# LEDSubMatrixHighDensity_template.net
KiCad netlist of a schematic drawn in EAGLE
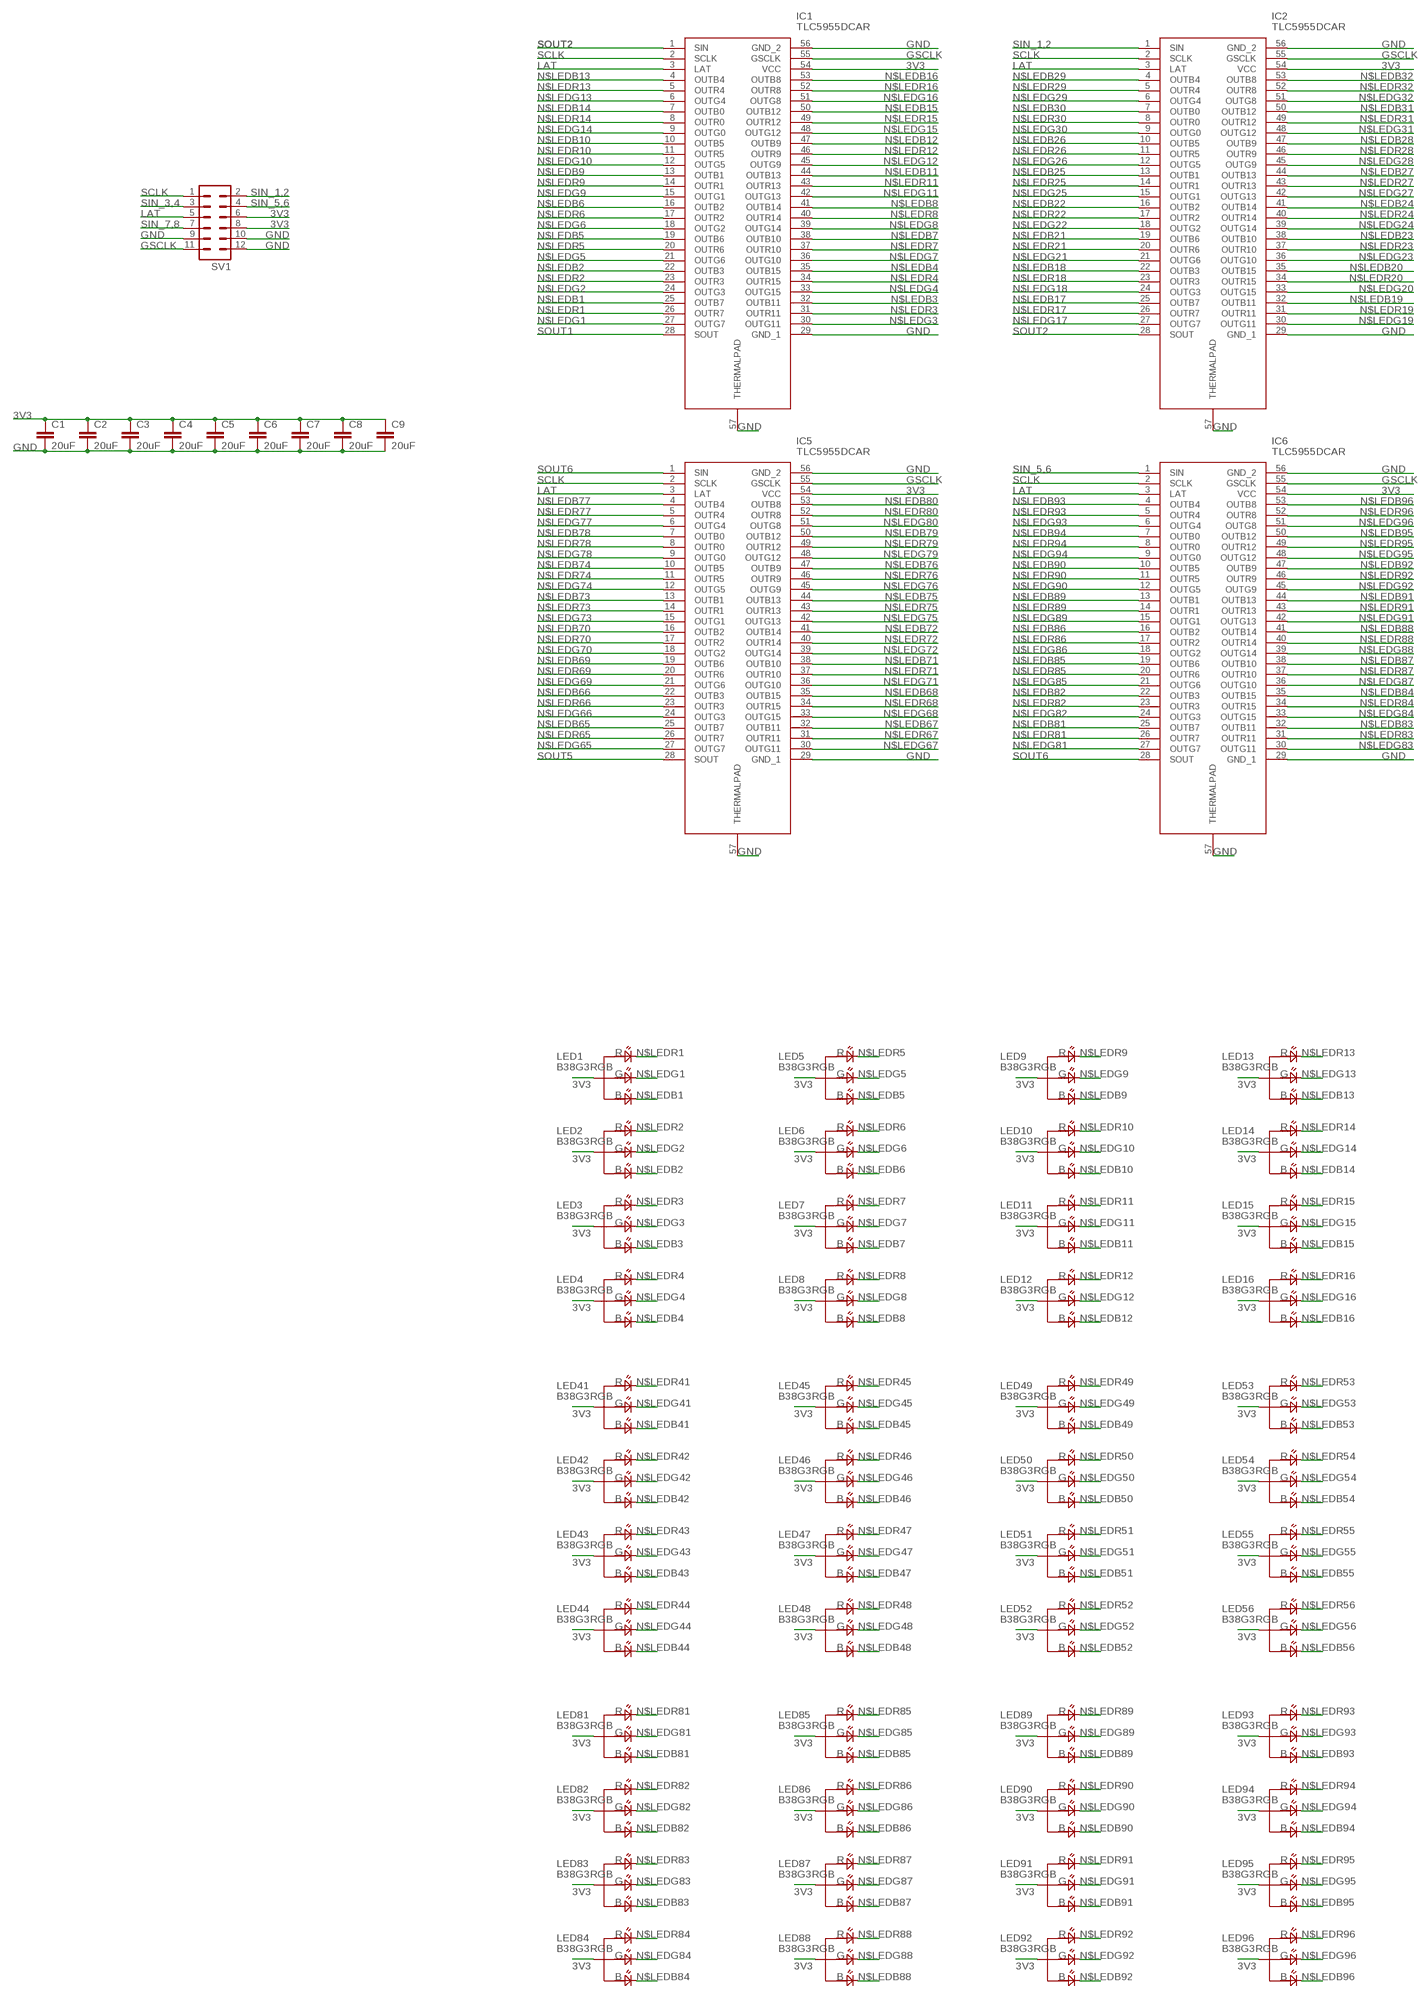
[diagram p0: schematic, sheet 1, part 1 of 2]
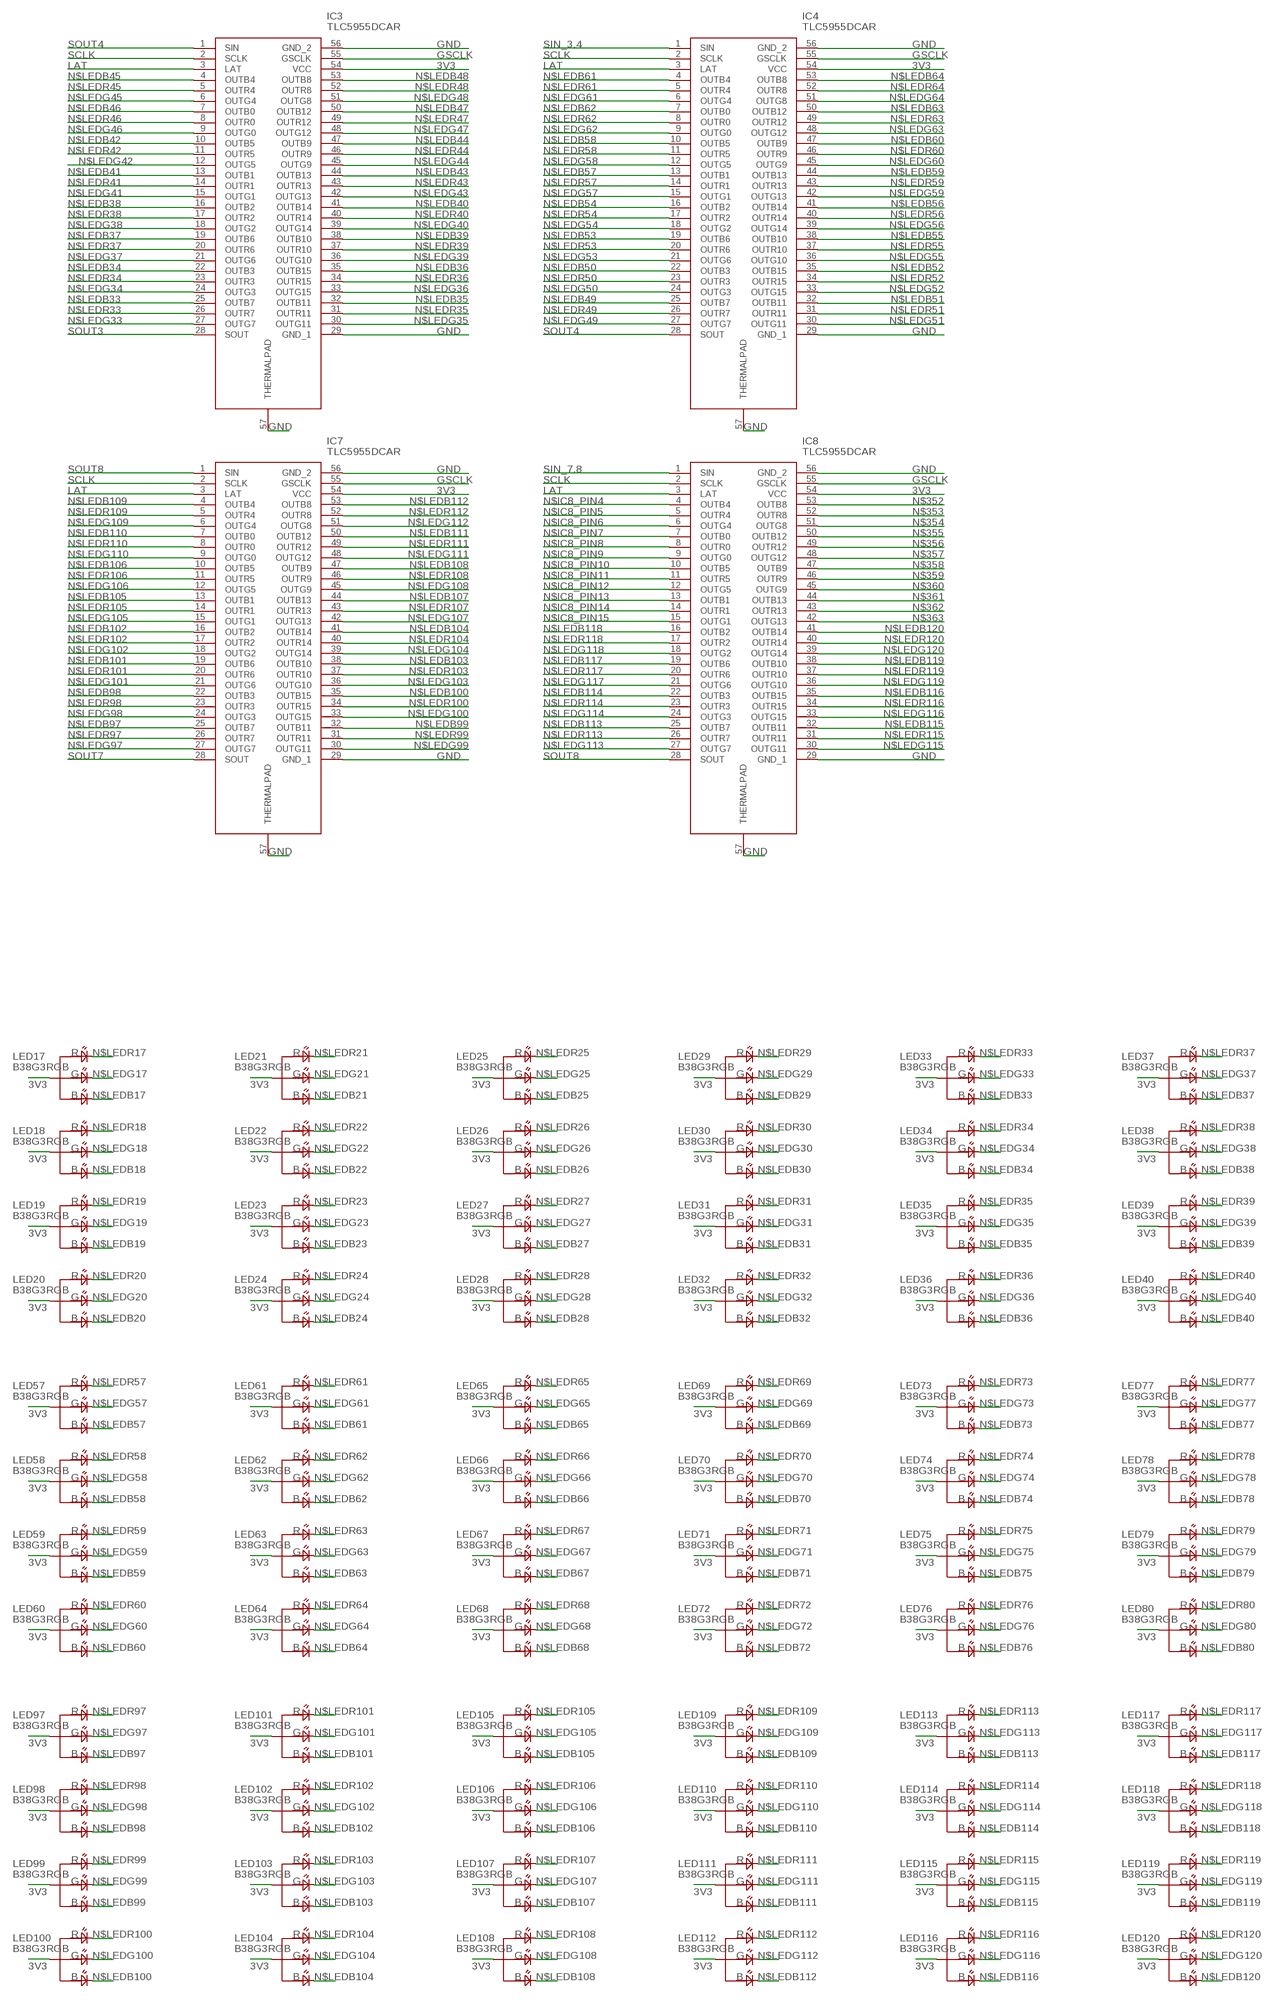
[diagram p1: schematic, sheet 1, part 2 of 2]

(export (version "E")
  (design (tool "Eeschema 10.0.6"))
  (components
    (comp (ref "C1")
      (value "20uF")
      (footprint "eagle-import:C0603")
      (libsource (lib "eagle-import") (part "C-EUC0603"))
    )
    (comp (ref "C2")
      (value "20uF")
      (footprint "eagle-import:C0603")
      (libsource (lib "eagle-import") (part "C-EUC0603"))
    )
    (comp (ref "C3")
      (value "20uF")
      (footprint "eagle-import:C0603")
      (libsource (lib "eagle-import") (part "C-EUC0603"))
    )
    (comp (ref "C4")
      (value "20uF")
      (footprint "eagle-import:C0603")
      (libsource (lib "eagle-import") (part "C-EUC0603"))
    )
    (comp (ref "C5")
      (value "20uF")
      (footprint "eagle-import:C0603")
      (libsource (lib "eagle-import") (part "C-EUC0603"))
    )
    (comp (ref "C6")
      (value "20uF")
      (footprint "eagle-import:C0603")
      (libsource (lib "eagle-import") (part "C-EUC0603"))
    )
    (comp (ref "C7")
      (value "20uF")
      (footprint "eagle-import:C0603")
      (libsource (lib "eagle-import") (part "C-EUC0603"))
    )
    (comp (ref "C8")
      (value "20uF")
      (footprint "eagle-import:C0603")
      (libsource (lib "eagle-import") (part "C-EUC0603"))
    )
    (comp (ref "C9")
      (value "20uF")
      (footprint "eagle-import:C0805")
      (libsource (lib "eagle-import") (part "C-EUC0805"))
    )
    (comp (ref "IC1")
      (value "TLC5955DCAR")
      (footprint "eagle-import:SOP50P810X120-57N")
      (fields (field (name "MOUSER_PART_NUMBER") "595-TLC5955DCAR"))
      (libsource (lib "eagle-import") (part "TLC5955DCAR"))
    )
    (comp (ref "IC2")
      (value "TLC5955DCAR")
      (footprint "eagle-import:SOP50P810X120-57N")
      (fields (field (name "MOUSER_PART_NUMBER") "595-TLC5955DCAR"))
      (libsource (lib "eagle-import") (part "TLC5955DCAR"))
    )
    (comp (ref "IC3")
      (value "TLC5955DCAR")
      (footprint "eagle-import:SOP50P810X120-57N")
      (fields (field (name "MOUSER_PART_NUMBER") "595-TLC5955DCAR"))
      (libsource (lib "eagle-import") (part "TLC5955DCAR"))
    )
    (comp (ref "IC4")
      (value "TLC5955DCAR")
      (footprint "eagle-import:SOP50P810X120-57N")
      (fields (field (name "MOUSER_PART_NUMBER") "595-TLC5955DCAR"))
      (libsource (lib "eagle-import") (part "TLC5955DCAR"))
    )
    (comp (ref "IC5")
      (value "TLC5955DCAR")
      (footprint "eagle-import:SOP50P810X120-57N")
      (fields (field (name "MOUSER_PART_NUMBER") "595-TLC5955DCAR"))
      (libsource (lib "eagle-import") (part "TLC5955DCAR"))
    )
    (comp (ref "IC6")
      (value "TLC5955DCAR")
      (footprint "eagle-import:SOP50P810X120-57N")
      (fields (field (name "MOUSER_PART_NUMBER") "595-TLC5955DCAR"))
      (libsource (lib "eagle-import") (part "TLC5955DCAR"))
    )
    (comp (ref "IC7")
      (value "TLC5955DCAR")
      (footprint "eagle-import:SOP50P810X120-57N")
      (fields (field (name "MOUSER_PART_NUMBER") "595-TLC5955DCAR"))
      (libsource (lib "eagle-import") (part "TLC5955DCAR"))
    )
    (comp (ref "IC8")
      (value "TLC5955DCAR")
      (footprint "eagle-import:SOP50P810X120-57N")
      (fields (field (name "MOUSER_PART_NUMBER") "595-TLC5955DCAR"))
      (libsource (lib "eagle-import") (part "TLC5955DCAR"))
    )
    (comp (ref "LED1")
      (value "B38G3RGB")
      (footprint "eagle-import:B38G3RGB")
      (fields
        (field (name "ARROW_PART_NUMBER") "SML-LX0606IGC-TR")
        (field (name "MOUSER_PART_NUMBER") "696-SML-0606IGCTR")
      )
      (libsource (lib "eagle-import") (part "B38G3RGB"))
    )
    (comp (ref "LED2")
      (value "B38G3RGB")
      (footprint "eagle-import:B38G3RGB")
      (fields
        (field (name "ARROW_PART_NUMBER") "SML-LX0606IGC-TR")
        (field (name "MOUSER_PART_NUMBER") "696-SML-0606IGCTR")
      )
      (libsource (lib "eagle-import") (part "B38G3RGB"))
    )
    (comp (ref "LED3")
      (value "B38G3RGB")
      (footprint "eagle-import:B38G3RGB")
      (fields
        (field (name "ARROW_PART_NUMBER") "SML-LX0606IGC-TR")
        (field (name "MOUSER_PART_NUMBER") "696-SML-0606IGCTR")
      )
      (libsource (lib "eagle-import") (part "B38G3RGB"))
    )
    (comp (ref "LED4")
      (value "B38G3RGB")
      (footprint "eagle-import:B38G3RGB")
      (fields
        (field (name "ARROW_PART_NUMBER") "SML-LX0606IGC-TR")
        (field (name "MOUSER_PART_NUMBER") "696-SML-0606IGCTR")
      )
      (libsource (lib "eagle-import") (part "B38G3RGB"))
    )
    (comp (ref "LED5")
      (value "B38G3RGB")
      (footprint "eagle-import:B38G3RGB")
      (fields
        (field (name "ARROW_PART_NUMBER") "SML-LX0606IGC-TR")
        (field (name "MOUSER_PART_NUMBER") "696-SML-0606IGCTR")
      )
      (libsource (lib "eagle-import") (part "B38G3RGB"))
    )
    (comp (ref "LED6")
      (value "B38G3RGB")
      (footprint "eagle-import:B38G3RGB")
      (fields
        (field (name "ARROW_PART_NUMBER") "SML-LX0606IGC-TR")
        (field (name "MOUSER_PART_NUMBER") "696-SML-0606IGCTR")
      )
      (libsource (lib "eagle-import") (part "B38G3RGB"))
    )
    (comp (ref "LED7")
      (value "B38G3RGB")
      (footprint "eagle-import:B38G3RGB")
      (fields
        (field (name "ARROW_PART_NUMBER") "SML-LX0606IGC-TR")
        (field (name "MOUSER_PART_NUMBER") "696-SML-0606IGCTR")
      )
      (libsource (lib "eagle-import") (part "B38G3RGB"))
    )
    (comp (ref "LED8")
      (value "B38G3RGB")
      (footprint "eagle-import:B38G3RGB")
      (fields
        (field (name "ARROW_PART_NUMBER") "SML-LX0606IGC-TR")
        (field (name "MOUSER_PART_NUMBER") "696-SML-0606IGCTR")
      )
      (libsource (lib "eagle-import") (part "B38G3RGB"))
    )
    (comp (ref "LED9")
      (value "B38G3RGB")
      (footprint "eagle-import:B38G3RGB")
      (fields
        (field (name "ARROW_PART_NUMBER") "SML-LX0606IGC-TR")
        (field (name "MOUSER_PART_NUMBER") "696-SML-0606IGCTR")
      )
      (libsource (lib "eagle-import") (part "B38G3RGB"))
    )
    (comp (ref "LED10")
      (value "B38G3RGB")
      (footprint "eagle-import:B38G3RGB")
      (fields
        (field (name "ARROW_PART_NUMBER") "SML-LX0606IGC-TR")
        (field (name "MOUSER_PART_NUMBER") "696-SML-0606IGCTR")
      )
      (libsource (lib "eagle-import") (part "B38G3RGB"))
    )
    (comp (ref "LED11")
      (value "B38G3RGB")
      (footprint "eagle-import:B38G3RGB")
      (fields
        (field (name "ARROW_PART_NUMBER") "SML-LX0606IGC-TR")
        (field (name "MOUSER_PART_NUMBER") "696-SML-0606IGCTR")
      )
      (libsource (lib "eagle-import") (part "B38G3RGB"))
    )
    (comp (ref "LED12")
      (value "B38G3RGB")
      (footprint "eagle-import:B38G3RGB")
      (fields
        (field (name "ARROW_PART_NUMBER") "SML-LX0606IGC-TR")
        (field (name "MOUSER_PART_NUMBER") "696-SML-0606IGCTR")
      )
      (libsource (lib "eagle-import") (part "B38G3RGB"))
    )
    (comp (ref "LED13")
      (value "B38G3RGB")
      (footprint "eagle-import:B38G3RGB")
      (fields
        (field (name "ARROW_PART_NUMBER") "SML-LX0606IGC-TR")
        (field (name "MOUSER_PART_NUMBER") "696-SML-0606IGCTR")
      )
      (libsource (lib "eagle-import") (part "B38G3RGB"))
    )
    (comp (ref "LED14")
      (value "B38G3RGB")
      (footprint "eagle-import:B38G3RGB")
      (fields
        (field (name "ARROW_PART_NUMBER") "SML-LX0606IGC-TR")
        (field (name "MOUSER_PART_NUMBER") "696-SML-0606IGCTR")
      )
      (libsource (lib "eagle-import") (part "B38G3RGB"))
    )
    (comp (ref "LED15")
      (value "B38G3RGB")
      (footprint "eagle-import:B38G3RGB")
      (fields
        (field (name "ARROW_PART_NUMBER") "SML-LX0606IGC-TR")
        (field (name "MOUSER_PART_NUMBER") "696-SML-0606IGCTR")
      )
      (libsource (lib "eagle-import") (part "B38G3RGB"))
    )
    (comp (ref "LED16")
      (value "B38G3RGB")
      (footprint "eagle-import:B38G3RGB")
      (fields
        (field (name "ARROW_PART_NUMBER") "SML-LX0606IGC-TR")
        (field (name "MOUSER_PART_NUMBER") "696-SML-0606IGCTR")
      )
      (libsource (lib "eagle-import") (part "B38G3RGB"))
    )
    (comp (ref "LED17")
      (value "B38G3RGB")
      (footprint "eagle-import:B38G3RGB")
      (fields
        (field (name "ARROW_PART_NUMBER") "SML-LX0606IGC-TR")
        (field (name "MOUSER_PART_NUMBER") "696-SML-0606IGCTR")
      )
      (libsource (lib "eagle-import") (part "B38G3RGB"))
    )
    (comp (ref "LED18")
      (value "B38G3RGB")
      (footprint "eagle-import:B38G3RGB")
      (fields
        (field (name "ARROW_PART_NUMBER") "SML-LX0606IGC-TR")
        (field (name "MOUSER_PART_NUMBER") "696-SML-0606IGCTR")
      )
      (libsource (lib "eagle-import") (part "B38G3RGB"))
    )
    (comp (ref "LED19")
      (value "B38G3RGB")
      (footprint "eagle-import:B38G3RGB")
      (fields
        (field (name "ARROW_PART_NUMBER") "SML-LX0606IGC-TR")
        (field (name "MOUSER_PART_NUMBER") "696-SML-0606IGCTR")
      )
      (libsource (lib "eagle-import") (part "B38G3RGB"))
    )
    (comp (ref "LED20")
      (value "B38G3RGB")
      (footprint "eagle-import:B38G3RGB")
      (fields
        (field (name "ARROW_PART_NUMBER") "SML-LX0606IGC-TR")
        (field (name "MOUSER_PART_NUMBER") "696-SML-0606IGCTR")
      )
      (libsource (lib "eagle-import") (part "B38G3RGB"))
    )
    (comp (ref "LED21")
      (value "B38G3RGB")
      (footprint "eagle-import:B38G3RGB")
      (fields
        (field (name "ARROW_PART_NUMBER") "SML-LX0606IGC-TR")
        (field (name "MOUSER_PART_NUMBER") "696-SML-0606IGCTR")
      )
      (libsource (lib "eagle-import") (part "B38G3RGB"))
    )
    (comp (ref "LED22")
      (value "B38G3RGB")
      (footprint "eagle-import:B38G3RGB")
      (fields
        (field (name "ARROW_PART_NUMBER") "SML-LX0606IGC-TR")
        (field (name "MOUSER_PART_NUMBER") "696-SML-0606IGCTR")
      )
      (libsource (lib "eagle-import") (part "B38G3RGB"))
    )
    (comp (ref "LED23")
      (value "B38G3RGB")
      (footprint "eagle-import:B38G3RGB")
      (fields
        (field (name "ARROW_PART_NUMBER") "SML-LX0606IGC-TR")
        (field (name "MOUSER_PART_NUMBER") "696-SML-0606IGCTR")
      )
      (libsource (lib "eagle-import") (part "B38G3RGB"))
    )
    (comp (ref "LED24")
      (value "B38G3RGB")
      (footprint "eagle-import:B38G3RGB")
      (fields
        (field (name "ARROW_PART_NUMBER") "SML-LX0606IGC-TR")
        (field (name "MOUSER_PART_NUMBER") "696-SML-0606IGCTR")
      )
      (libsource (lib "eagle-import") (part "B38G3RGB"))
    )
    (comp (ref "LED25")
      (value "B38G3RGB")
      (footprint "eagle-import:B38G3RGB")
      (fields
        (field (name "ARROW_PART_NUMBER") "SML-LX0606IGC-TR")
        (field (name "MOUSER_PART_NUMBER") "696-SML-0606IGCTR")
      )
      (libsource (lib "eagle-import") (part "B38G3RGB"))
    )
    (comp (ref "LED26")
      (value "B38G3RGB")
      (footprint "eagle-import:B38G3RGB")
      (fields
        (field (name "ARROW_PART_NUMBER") "SML-LX0606IGC-TR")
        (field (name "MOUSER_PART_NUMBER") "696-SML-0606IGCTR")
      )
      (libsource (lib "eagle-import") (part "B38G3RGB"))
    )
    (comp (ref "LED27")
      (value "B38G3RGB")
      (footprint "eagle-import:B38G3RGB")
      (fields
        (field (name "ARROW_PART_NUMBER") "SML-LX0606IGC-TR")
        (field (name "MOUSER_PART_NUMBER") "696-SML-0606IGCTR")
      )
      (libsource (lib "eagle-import") (part "B38G3RGB"))
    )
    (comp (ref "LED28")
      (value "B38G3RGB")
      (footprint "eagle-import:B38G3RGB")
      (fields
        (field (name "ARROW_PART_NUMBER") "SML-LX0606IGC-TR")
        (field (name "MOUSER_PART_NUMBER") "696-SML-0606IGCTR")
      )
      (libsource (lib "eagle-import") (part "B38G3RGB"))
    )
    (comp (ref "LED29")
      (value "B38G3RGB")
      (footprint "eagle-import:B38G3RGB")
      (fields
        (field (name "ARROW_PART_NUMBER") "SML-LX0606IGC-TR")
        (field (name "MOUSER_PART_NUMBER") "696-SML-0606IGCTR")
      )
      (libsource (lib "eagle-import") (part "B38G3RGB"))
    )
    (comp (ref "LED30")
      (value "B38G3RGB")
      (footprint "eagle-import:B38G3RGB")
      (fields
        (field (name "ARROW_PART_NUMBER") "SML-LX0606IGC-TR")
        (field (name "MOUSER_PART_NUMBER") "696-SML-0606IGCTR")
      )
      (libsource (lib "eagle-import") (part "B38G3RGB"))
    )
    (comp (ref "LED31")
      (value "B38G3RGB")
      (footprint "eagle-import:B38G3RGB")
      (fields
        (field (name "ARROW_PART_NUMBER") "SML-LX0606IGC-TR")
        (field (name "MOUSER_PART_NUMBER") "696-SML-0606IGCTR")
      )
      (libsource (lib "eagle-import") (part "B38G3RGB"))
    )
    (comp (ref "LED32")
      (value "B38G3RGB")
      (footprint "eagle-import:B38G3RGB")
      (fields
        (field (name "ARROW_PART_NUMBER") "SML-LX0606IGC-TR")
        (field (name "MOUSER_PART_NUMBER") "696-SML-0606IGCTR")
      )
      (libsource (lib "eagle-import") (part "B38G3RGB"))
    )
    (comp (ref "LED33")
      (value "B38G3RGB")
      (footprint "eagle-import:B38G3RGB")
      (fields
        (field (name "ARROW_PART_NUMBER") "SML-LX0606IGC-TR")
        (field (name "MOUSER_PART_NUMBER") "696-SML-0606IGCTR")
      )
      (libsource (lib "eagle-import") (part "B38G3RGB"))
    )
    (comp (ref "LED34")
      (value "B38G3RGB")
      (footprint "eagle-import:B38G3RGB")
      (fields
        (field (name "ARROW_PART_NUMBER") "SML-LX0606IGC-TR")
        (field (name "MOUSER_PART_NUMBER") "696-SML-0606IGCTR")
      )
      (libsource (lib "eagle-import") (part "B38G3RGB"))
    )
    (comp (ref "LED35")
      (value "B38G3RGB")
      (footprint "eagle-import:B38G3RGB")
      (fields
        (field (name "ARROW_PART_NUMBER") "SML-LX0606IGC-TR")
        (field (name "MOUSER_PART_NUMBER") "696-SML-0606IGCTR")
      )
      (libsource (lib "eagle-import") (part "B38G3RGB"))
    )
    (comp (ref "LED36")
      (value "B38G3RGB")
      (footprint "eagle-import:B38G3RGB")
      (fields
        (field (name "ARROW_PART_NUMBER") "SML-LX0606IGC-TR")
        (field (name "MOUSER_PART_NUMBER") "696-SML-0606IGCTR")
      )
      (libsource (lib "eagle-import") (part "B38G3RGB"))
    )
    (comp (ref "LED37")
      (value "B38G3RGB")
      (footprint "eagle-import:B38G3RGB")
      (fields
        (field (name "ARROW_PART_NUMBER") "SML-LX0606IGC-TR")
        (field (name "MOUSER_PART_NUMBER") "696-SML-0606IGCTR")
      )
      (libsource (lib "eagle-import") (part "B38G3RGB"))
    )
    (comp (ref "LED38")
      (value "B38G3RGB")
      (footprint "eagle-import:B38G3RGB")
      (fields
        (field (name "ARROW_PART_NUMBER") "SML-LX0606IGC-TR")
        (field (name "MOUSER_PART_NUMBER") "696-SML-0606IGCTR")
      )
      (libsource (lib "eagle-import") (part "B38G3RGB"))
    )
    (comp (ref "LED39")
      (value "B38G3RGB")
      (footprint "eagle-import:B38G3RGB")
      (fields
        (field (name "ARROW_PART_NUMBER") "SML-LX0606IGC-TR")
        (field (name "MOUSER_PART_NUMBER") "696-SML-0606IGCTR")
      )
      (libsource (lib "eagle-import") (part "B38G3RGB"))
    )
    (comp (ref "LED40")
      (value "B38G3RGB")
      (footprint "eagle-import:B38G3RGB")
      (fields
        (field (name "ARROW_PART_NUMBER") "SML-LX0606IGC-TR")
        (field (name "MOUSER_PART_NUMBER") "696-SML-0606IGCTR")
      )
      (libsource (lib "eagle-import") (part "B38G3RGB"))
    )
    (comp (ref "LED41")
      (value "B38G3RGB")
      (footprint "eagle-import:B38G3RGB")
      (fields
        (field (name "ARROW_PART_NUMBER") "SML-LX0606IGC-TR")
        (field (name "MOUSER_PART_NUMBER") "696-SML-0606IGCTR")
      )
      (libsource (lib "eagle-import") (part "B38G3RGB"))
    )
    (comp (ref "LED42")
      (value "B38G3RGB")
      (footprint "eagle-import:B38G3RGB")
      (fields
        (field (name "ARROW_PART_NUMBER") "SML-LX0606IGC-TR")
        (field (name "MOUSER_PART_NUMBER") "696-SML-0606IGCTR")
      )
      (libsource (lib "eagle-import") (part "B38G3RGB"))
    )
    (comp (ref "LED43")
      (value "B38G3RGB")
      (footprint "eagle-import:B38G3RGB")
      (fields
        (field (name "ARROW_PART_NUMBER") "SML-LX0606IGC-TR")
        (field (name "MOUSER_PART_NUMBER") "696-SML-0606IGCTR")
      )
      (libsource (lib "eagle-import") (part "B38G3RGB"))
    )
    (comp (ref "LED44")
      (value "B38G3RGB")
      (footprint "eagle-import:B38G3RGB")
      (fields
        (field (name "ARROW_PART_NUMBER") "SML-LX0606IGC-TR")
        (field (name "MOUSER_PART_NUMBER") "696-SML-0606IGCTR")
      )
      (libsource (lib "eagle-import") (part "B38G3RGB"))
    )
    (comp (ref "LED45")
      (value "B38G3RGB")
      (footprint "eagle-import:B38G3RGB")
      (fields
        (field (name "ARROW_PART_NUMBER") "SML-LX0606IGC-TR")
        (field (name "MOUSER_PART_NUMBER") "696-SML-0606IGCTR")
      )
      (libsource (lib "eagle-import") (part "B38G3RGB"))
    )
    (comp (ref "LED46")
      (value "B38G3RGB")
      (footprint "eagle-import:B38G3RGB")
      (fields
        (field (name "ARROW_PART_NUMBER") "SML-LX0606IGC-TR")
        (field (name "MOUSER_PART_NUMBER") "696-SML-0606IGCTR")
      )
      (libsource (lib "eagle-import") (part "B38G3RGB"))
    )
    (comp (ref "LED47")
      (value "B38G3RGB")
      (footprint "eagle-import:B38G3RGB")
      (fields
        (field (name "ARROW_PART_NUMBER") "SML-LX0606IGC-TR")
        (field (name "MOUSER_PART_NUMBER") "696-SML-0606IGCTR")
      )
      (libsource (lib "eagle-import") (part "B38G3RGB"))
    )
    (comp (ref "LED48")
      (value "B38G3RGB")
      (footprint "eagle-import:B38G3RGB")
      (fields
        (field (name "ARROW_PART_NUMBER") "SML-LX0606IGC-TR")
        (field (name "MOUSER_PART_NUMBER") "696-SML-0606IGCTR")
      )
      (libsource (lib "eagle-import") (part "B38G3RGB"))
    )
    (comp (ref "LED49")
      (value "B38G3RGB")
      (footprint "eagle-import:B38G3RGB")
      (fields
        (field (name "ARROW_PART_NUMBER") "SML-LX0606IGC-TR")
        (field (name "MOUSER_PART_NUMBER") "696-SML-0606IGCTR")
      )
      (libsource (lib "eagle-import") (part "B38G3RGB"))
    )
    (comp (ref "LED50")
      (value "B38G3RGB")
      (footprint "eagle-import:B38G3RGB")
      (fields
        (field (name "ARROW_PART_NUMBER") "SML-LX0606IGC-TR")
        (field (name "MOUSER_PART_NUMBER") "696-SML-0606IGCTR")
      )
      (libsource (lib "eagle-import") (part "B38G3RGB"))
    )
    (comp (ref "LED51")
      (value "B38G3RGB")
      (footprint "eagle-import:B38G3RGB")
      (fields
        (field (name "ARROW_PART_NUMBER") "SML-LX0606IGC-TR")
        (field (name "MOUSER_PART_NUMBER") "696-SML-0606IGCTR")
      )
      (libsource (lib "eagle-import") (part "B38G3RGB"))
    )
    (comp (ref "LED52")
      (value "B38G3RGB")
      (footprint "eagle-import:B38G3RGB")
      (fields
        (field (name "ARROW_PART_NUMBER") "SML-LX0606IGC-TR")
        (field (name "MOUSER_PART_NUMBER") "696-SML-0606IGCTR")
      )
      (libsource (lib "eagle-import") (part "B38G3RGB"))
    )
    (comp (ref "LED53")
      (value "B38G3RGB")
      (footprint "eagle-import:B38G3RGB")
      (fields
        (field (name "ARROW_PART_NUMBER") "SML-LX0606IGC-TR")
        (field (name "MOUSER_PART_NUMBER") "696-SML-0606IGCTR")
      )
      (libsource (lib "eagle-import") (part "B38G3RGB"))
    )
    (comp (ref "LED54")
      (value "B38G3RGB")
      (footprint "eagle-import:B38G3RGB")
      (fields
        (field (name "ARROW_PART_NUMBER") "SML-LX0606IGC-TR")
        (field (name "MOUSER_PART_NUMBER") "696-SML-0606IGCTR")
      )
      (libsource (lib "eagle-import") (part "B38G3RGB"))
    )
    (comp (ref "LED55")
      (value "B38G3RGB")
      (footprint "eagle-import:B38G3RGB")
      (fields
        (field (name "ARROW_PART_NUMBER") "SML-LX0606IGC-TR")
        (field (name "MOUSER_PART_NUMBER") "696-SML-0606IGCTR")
      )
      (libsource (lib "eagle-import") (part "B38G3RGB"))
    )
    (comp (ref "LED56")
      (value "B38G3RGB")
      (footprint "eagle-import:B38G3RGB")
      (fields
        (field (name "ARROW_PART_NUMBER") "SML-LX0606IGC-TR")
        (field (name "MOUSER_PART_NUMBER") "696-SML-0606IGCTR")
      )
      (libsource (lib "eagle-import") (part "B38G3RGB"))
    )
    (comp (ref "LED57")
      (value "B38G3RGB")
      (footprint "eagle-import:B38G3RGB")
      (fields
        (field (name "ARROW_PART_NUMBER") "SML-LX0606IGC-TR")
        (field (name "MOUSER_PART_NUMBER") "696-SML-0606IGCTR")
      )
      (libsource (lib "eagle-import") (part "B38G3RGB"))
    )
    (comp (ref "LED58")
      (value "B38G3RGB")
      (footprint "eagle-import:B38G3RGB")
      (fields
        (field (name "ARROW_PART_NUMBER") "SML-LX0606IGC-TR")
        (field (name "MOUSER_PART_NUMBER") "696-SML-0606IGCTR")
      )
      (libsource (lib "eagle-import") (part "B38G3RGB"))
    )
    (comp (ref "LED59")
      (value "B38G3RGB")
      (footprint "eagle-import:B38G3RGB")
      (fields
        (field (name "ARROW_PART_NUMBER") "SML-LX0606IGC-TR")
        (field (name "MOUSER_PART_NUMBER") "696-SML-0606IGCTR")
      )
      (libsource (lib "eagle-import") (part "B38G3RGB"))
    )
    (comp (ref "LED60")
      (value "B38G3RGB")
      (footprint "eagle-import:B38G3RGB")
      (fields
        (field (name "ARROW_PART_NUMBER") "SML-LX0606IGC-TR")
        (field (name "MOUSER_PART_NUMBER") "696-SML-0606IGCTR")
      )
      (libsource (lib "eagle-import") (part "B38G3RGB"))
    )
    (comp (ref "LED61")
      (value "B38G3RGB")
      (footprint "eagle-import:B38G3RGB")
      (fields
        (field (name "ARROW_PART_NUMBER") "SML-LX0606IGC-TR")
        (field (name "MOUSER_PART_NUMBER") "696-SML-0606IGCTR")
      )
      (libsource (lib "eagle-import") (part "B38G3RGB"))
    )
    (comp (ref "LED62")
      (value "B38G3RGB")
      (footprint "eagle-import:B38G3RGB")
      (fields
        (field (name "ARROW_PART_NUMBER") "SML-LX0606IGC-TR")
        (field (name "MOUSER_PART_NUMBER") "696-SML-0606IGCTR")
      )
      (libsource (lib "eagle-import") (part "B38G3RGB"))
    )
    (comp (ref "LED63")
      (value "B38G3RGB")
      (footprint "eagle-import:B38G3RGB")
      (fields
        (field (name "ARROW_PART_NUMBER") "SML-LX0606IGC-TR")
        (field (name "MOUSER_PART_NUMBER") "696-SML-0606IGCTR")
      )
      (libsource (lib "eagle-import") (part "B38G3RGB"))
    )
    (comp (ref "LED64")
      (value "B38G3RGB")
      (footprint "eagle-import:B38G3RGB")
      (fields
        (field (name "ARROW_PART_NUMBER") "SML-LX0606IGC-TR")
        (field (name "MOUSER_PART_NUMBER") "696-SML-0606IGCTR")
      )
      (libsource (lib "eagle-import") (part "B38G3RGB"))
    )
    (comp (ref "LED65")
      (value "B38G3RGB")
      (footprint "eagle-import:B38G3RGB")
      (fields
        (field (name "ARROW_PART_NUMBER") "SML-LX0606IGC-TR")
        (field (name "MOUSER_PART_NUMBER") "696-SML-0606IGCTR")
      )
      (libsource (lib "eagle-import") (part "B38G3RGB"))
    )
    (comp (ref "LED66")
      (value "B38G3RGB")
      (footprint "eagle-import:B38G3RGB")
      (fields
        (field (name "ARROW_PART_NUMBER") "SML-LX0606IGC-TR")
        (field (name "MOUSER_PART_NUMBER") "696-SML-0606IGCTR")
      )
      (libsource (lib "eagle-import") (part "B38G3RGB"))
    )
    (comp (ref "LED67")
      (value "B38G3RGB")
      (footprint "eagle-import:B38G3RGB")
      (fields
        (field (name "ARROW_PART_NUMBER") "SML-LX0606IGC-TR")
        (field (name "MOUSER_PART_NUMBER") "696-SML-0606IGCTR")
      )
      (libsource (lib "eagle-import") (part "B38G3RGB"))
    )
    (comp (ref "LED68")
      (value "B38G3RGB")
      (footprint "eagle-import:B38G3RGB")
      (fields
        (field (name "ARROW_PART_NUMBER") "SML-LX0606IGC-TR")
        (field (name "MOUSER_PART_NUMBER") "696-SML-0606IGCTR")
      )
      (libsource (lib "eagle-import") (part "B38G3RGB"))
    )
    (comp (ref "LED69")
      (value "B38G3RGB")
      (footprint "eagle-import:B38G3RGB")
      (fields
        (field (name "ARROW_PART_NUMBER") "SML-LX0606IGC-TR")
        (field (name "MOUSER_PART_NUMBER") "696-SML-0606IGCTR")
      )
      (libsource (lib "eagle-import") (part "B38G3RGB"))
    )
    (comp (ref "LED70")
      (value "B38G3RGB")
      (footprint "eagle-import:B38G3RGB")
      (fields
        (field (name "ARROW_PART_NUMBER") "SML-LX0606IGC-TR")
        (field (name "MOUSER_PART_NUMBER") "696-SML-0606IGCTR")
      )
      (libsource (lib "eagle-import") (part "B38G3RGB"))
    )
    (comp (ref "LED71")
      (value "B38G3RGB")
      (footprint "eagle-import:B38G3RGB")
      (fields
        (field (name "ARROW_PART_NUMBER") "SML-LX0606IGC-TR")
        (field (name "MOUSER_PART_NUMBER") "696-SML-0606IGCTR")
      )
      (libsource (lib "eagle-import") (part "B38G3RGB"))
    )
    (comp (ref "LED72")
      (value "B38G3RGB")
      (footprint "eagle-import:B38G3RGB")
      (fields
        (field (name "ARROW_PART_NUMBER") "SML-LX0606IGC-TR")
        (field (name "MOUSER_PART_NUMBER") "696-SML-0606IGCTR")
      )
      (libsource (lib "eagle-import") (part "B38G3RGB"))
    )
    (comp (ref "LED73")
      (value "B38G3RGB")
      (footprint "eagle-import:B38G3RGB")
      (fields
        (field (name "ARROW_PART_NUMBER") "SML-LX0606IGC-TR")
        (field (name "MOUSER_PART_NUMBER") "696-SML-0606IGCTR")
      )
      (libsource (lib "eagle-import") (part "B38G3RGB"))
    )
    (comp (ref "LED74")
      (value "B38G3RGB")
      (footprint "eagle-import:B38G3RGB")
      (fields
        (field (name "ARROW_PART_NUMBER") "SML-LX0606IGC-TR")
        (field (name "MOUSER_PART_NUMBER") "696-SML-0606IGCTR")
      )
      (libsource (lib "eagle-import") (part "B38G3RGB"))
    )
    (comp (ref "LED75")
      (value "B38G3RGB")
      (footprint "eagle-import:B38G3RGB")
      (fields
        (field (name "ARROW_PART_NUMBER") "SML-LX0606IGC-TR")
        (field (name "MOUSER_PART_NUMBER") "696-SML-0606IGCTR")
      )
      (libsource (lib "eagle-import") (part "B38G3RGB"))
    )
    (comp (ref "LED76")
      (value "B38G3RGB")
      (footprint "eagle-import:B38G3RGB")
      (fields
        (field (name "ARROW_PART_NUMBER") "SML-LX0606IGC-TR")
        (field (name "MOUSER_PART_NUMBER") "696-SML-0606IGCTR")
      )
      (libsource (lib "eagle-import") (part "B38G3RGB"))
    )
    (comp (ref "LED77")
      (value "B38G3RGB")
      (footprint "eagle-import:B38G3RGB")
      (fields
        (field (name "ARROW_PART_NUMBER") "SML-LX0606IGC-TR")
        (field (name "MOUSER_PART_NUMBER") "696-SML-0606IGCTR")
      )
      (libsource (lib "eagle-import") (part "B38G3RGB"))
    )
    (comp (ref "LED78")
      (value "B38G3RGB")
      (footprint "eagle-import:B38G3RGB")
      (fields
        (field (name "ARROW_PART_NUMBER") "SML-LX0606IGC-TR")
        (field (name "MOUSER_PART_NUMBER") "696-SML-0606IGCTR")
      )
      (libsource (lib "eagle-import") (part "B38G3RGB"))
    )
    (comp (ref "LED79")
      (value "B38G3RGB")
      (footprint "eagle-import:B38G3RGB")
      (fields
        (field (name "ARROW_PART_NUMBER") "SML-LX0606IGC-TR")
        (field (name "MOUSER_PART_NUMBER") "696-SML-0606IGCTR")
      )
      (libsource (lib "eagle-import") (part "B38G3RGB"))
    )
    (comp (ref "LED80")
      (value "B38G3RGB")
      (footprint "eagle-import:B38G3RGB")
      (fields
        (field (name "ARROW_PART_NUMBER") "SML-LX0606IGC-TR")
        (field (name "MOUSER_PART_NUMBER") "696-SML-0606IGCTR")
      )
      (libsource (lib "eagle-import") (part "B38G3RGB"))
    )
    (comp (ref "LED81")
      (value "B38G3RGB")
      (footprint "eagle-import:B38G3RGB")
      (fields
        (field (name "ARROW_PART_NUMBER") "SML-LX0606IGC-TR")
        (field (name "MOUSER_PART_NUMBER") "696-SML-0606IGCTR")
      )
      (libsource (lib "eagle-import") (part "B38G3RGB"))
    )
    (comp (ref "LED82")
      (value "B38G3RGB")
      (footprint "eagle-import:B38G3RGB")
      (fields
        (field (name "ARROW_PART_NUMBER") "SML-LX0606IGC-TR")
        (field (name "MOUSER_PART_NUMBER") "696-SML-0606IGCTR")
      )
      (libsource (lib "eagle-import") (part "B38G3RGB"))
    )
    (comp (ref "LED83")
      (value "B38G3RGB")
      (footprint "eagle-import:B38G3RGB")
      (fields
        (field (name "ARROW_PART_NUMBER") "SML-LX0606IGC-TR")
        (field (name "MOUSER_PART_NUMBER") "696-SML-0606IGCTR")
      )
      (libsource (lib "eagle-import") (part "B38G3RGB"))
    )
    (comp (ref "LED84")
      (value "B38G3RGB")
      (footprint "eagle-import:B38G3RGB")
      (fields
        (field (name "ARROW_PART_NUMBER") "SML-LX0606IGC-TR")
        (field (name "MOUSER_PART_NUMBER") "696-SML-0606IGCTR")
      )
      (libsource (lib "eagle-import") (part "B38G3RGB"))
    )
    (comp (ref "LED85")
      (value "B38G3RGB")
      (footprint "eagle-import:B38G3RGB")
      (fields
        (field (name "ARROW_PART_NUMBER") "SML-LX0606IGC-TR")
        (field (name "MOUSER_PART_NUMBER") "696-SML-0606IGCTR")
      )
      (libsource (lib "eagle-import") (part "B38G3RGB"))
    )
    (comp (ref "LED86")
      (value "B38G3RGB")
      (footprint "eagle-import:B38G3RGB")
      (fields
        (field (name "ARROW_PART_NUMBER") "SML-LX0606IGC-TR")
        (field (name "MOUSER_PART_NUMBER") "696-SML-0606IGCTR")
      )
      (libsource (lib "eagle-import") (part "B38G3RGB"))
    )
    (comp (ref "LED87")
      (value "B38G3RGB")
      (footprint "eagle-import:B38G3RGB")
      (fields
        (field (name "ARROW_PART_NUMBER") "SML-LX0606IGC-TR")
        (field (name "MOUSER_PART_NUMBER") "696-SML-0606IGCTR")
      )
      (libsource (lib "eagle-import") (part "B38G3RGB"))
    )
    (comp (ref "LED88")
      (value "B38G3RGB")
      (footprint "eagle-import:B38G3RGB")
      (fields
        (field (name "ARROW_PART_NUMBER") "SML-LX0606IGC-TR")
        (field (name "MOUSER_PART_NUMBER") "696-SML-0606IGCTR")
      )
      (libsource (lib "eagle-import") (part "B38G3RGB"))
    )
    (comp (ref "LED89")
      (value "B38G3RGB")
      (footprint "eagle-import:B38G3RGB")
      (fields
        (field (name "ARROW_PART_NUMBER") "SML-LX0606IGC-TR")
        (field (name "MOUSER_PART_NUMBER") "696-SML-0606IGCTR")
      )
      (libsource (lib "eagle-import") (part "B38G3RGB"))
    )
    (comp (ref "LED90")
      (value "B38G3RGB")
      (footprint "eagle-import:B38G3RGB")
      (fields
        (field (name "ARROW_PART_NUMBER") "SML-LX0606IGC-TR")
        (field (name "MOUSER_PART_NUMBER") "696-SML-0606IGCTR")
      )
      (libsource (lib "eagle-import") (part "B38G3RGB"))
    )
    (comp (ref "LED91")
      (value "B38G3RGB")
      (footprint "eagle-import:B38G3RGB")
      (fields
        (field (name "ARROW_PART_NUMBER") "SML-LX0606IGC-TR")
        (field (name "MOUSER_PART_NUMBER") "696-SML-0606IGCTR")
      )
      (libsource (lib "eagle-import") (part "B38G3RGB"))
    )
    (comp (ref "LED92")
      (value "B38G3RGB")
      (footprint "eagle-import:B38G3RGB")
      (fields
        (field (name "ARROW_PART_NUMBER") "SML-LX0606IGC-TR")
        (field (name "MOUSER_PART_NUMBER") "696-SML-0606IGCTR")
      )
      (libsource (lib "eagle-import") (part "B38G3RGB"))
    )
    (comp (ref "LED93")
      (value "B38G3RGB")
      (footprint "eagle-import:B38G3RGB")
      (fields
        (field (name "ARROW_PART_NUMBER") "SML-LX0606IGC-TR")
        (field (name "MOUSER_PART_NUMBER") "696-SML-0606IGCTR")
      )
      (libsource (lib "eagle-import") (part "B38G3RGB"))
    )
    (comp (ref "LED94")
      (value "B38G3RGB")
      (footprint "eagle-import:B38G3RGB")
      (fields
        (field (name "ARROW_PART_NUMBER") "SML-LX0606IGC-TR")
        (field (name "MOUSER_PART_NUMBER") "696-SML-0606IGCTR")
      )
      (libsource (lib "eagle-import") (part "B38G3RGB"))
    )
    (comp (ref "LED95")
      (value "B38G3RGB")
      (footprint "eagle-import:B38G3RGB")
      (fields
        (field (name "ARROW_PART_NUMBER") "SML-LX0606IGC-TR")
        (field (name "MOUSER_PART_NUMBER") "696-SML-0606IGCTR")
      )
      (libsource (lib "eagle-import") (part "B38G3RGB"))
    )
    (comp (ref "LED96")
      (value "B38G3RGB")
      (footprint "eagle-import:B38G3RGB")
      (fields
        (field (name "ARROW_PART_NUMBER") "SML-LX0606IGC-TR")
        (field (name "MOUSER_PART_NUMBER") "696-SML-0606IGCTR")
      )
      (libsource (lib "eagle-import") (part "B38G3RGB"))
    )
    (comp (ref "LED97")
      (value "B38G3RGB")
      (footprint "eagle-import:B38G3RGB")
      (fields
        (field (name "ARROW_PART_NUMBER") "SML-LX0606IGC-TR")
        (field (name "MOUSER_PART_NUMBER") "696-SML-0606IGCTR")
      )
      (libsource (lib "eagle-import") (part "B38G3RGB"))
    )
    (comp (ref "LED98")
      (value "B38G3RGB")
      (footprint "eagle-import:B38G3RGB")
      (fields
        (field (name "ARROW_PART_NUMBER") "SML-LX0606IGC-TR")
        (field (name "MOUSER_PART_NUMBER") "696-SML-0606IGCTR")
      )
      (libsource (lib "eagle-import") (part "B38G3RGB"))
    )
    (comp (ref "LED99")
      (value "B38G3RGB")
      (footprint "eagle-import:B38G3RGB")
      (fields
        (field (name "ARROW_PART_NUMBER") "SML-LX0606IGC-TR")
        (field (name "MOUSER_PART_NUMBER") "696-SML-0606IGCTR")
      )
      (libsource (lib "eagle-import") (part "B38G3RGB"))
    )
    (comp (ref "LED100")
      (value "B38G3RGB")
      (footprint "eagle-import:B38G3RGB")
      (fields
        (field (name "ARROW_PART_NUMBER") "SML-LX0606IGC-TR")
        (field (name "MOUSER_PART_NUMBER") "696-SML-0606IGCTR")
      )
      (libsource (lib "eagle-import") (part "B38G3RGB"))
    )
    (comp (ref "LED101")
      (value "B38G3RGB")
      (footprint "eagle-import:B38G3RGB")
      (fields
        (field (name "ARROW_PART_NUMBER") "SML-LX0606IGC-TR")
        (field (name "MOUSER_PART_NUMBER") "696-SML-0606IGCTR")
      )
      (libsource (lib "eagle-import") (part "B38G3RGB"))
    )
    (comp (ref "LED102")
      (value "B38G3RGB")
      (footprint "eagle-import:B38G3RGB")
      (fields
        (field (name "ARROW_PART_NUMBER") "SML-LX0606IGC-TR")
        (field (name "MOUSER_PART_NUMBER") "696-SML-0606IGCTR")
      )
      (libsource (lib "eagle-import") (part "B38G3RGB"))
    )
    (comp (ref "LED103")
      (value "B38G3RGB")
      (footprint "eagle-import:B38G3RGB")
      (fields
        (field (name "ARROW_PART_NUMBER") "SML-LX0606IGC-TR")
        (field (name "MOUSER_PART_NUMBER") "696-SML-0606IGCTR")
      )
      (libsource (lib "eagle-import") (part "B38G3RGB"))
    )
    (comp (ref "LED104")
      (value "B38G3RGB")
      (footprint "eagle-import:B38G3RGB")
      (fields
        (field (name "ARROW_PART_NUMBER") "SML-LX0606IGC-TR")
        (field (name "MOUSER_PART_NUMBER") "696-SML-0606IGCTR")
      )
      (libsource (lib "eagle-import") (part "B38G3RGB"))
    )
    (comp (ref "LED105")
      (value "B38G3RGB")
      (footprint "eagle-import:B38G3RGB")
      (fields
        (field (name "ARROW_PART_NUMBER") "SML-LX0606IGC-TR")
        (field (name "MOUSER_PART_NUMBER") "696-SML-0606IGCTR")
      )
      (libsource (lib "eagle-import") (part "B38G3RGB"))
    )
    (comp (ref "LED106")
      (value "B38G3RGB")
      (footprint "eagle-import:B38G3RGB")
      (fields
        (field (name "ARROW_PART_NUMBER") "SML-LX0606IGC-TR")
        (field (name "MOUSER_PART_NUMBER") "696-SML-0606IGCTR")
      )
      (libsource (lib "eagle-import") (part "B38G3RGB"))
    )
    (comp (ref "LED107")
      (value "B38G3RGB")
      (footprint "eagle-import:B38G3RGB")
      (fields
        (field (name "ARROW_PART_NUMBER") "SML-LX0606IGC-TR")
        (field (name "MOUSER_PART_NUMBER") "696-SML-0606IGCTR")
      )
      (libsource (lib "eagle-import") (part "B38G3RGB"))
    )
    (comp (ref "LED108")
      (value "B38G3RGB")
      (footprint "eagle-import:B38G3RGB")
      (fields
        (field (name "ARROW_PART_NUMBER") "SML-LX0606IGC-TR")
        (field (name "MOUSER_PART_NUMBER") "696-SML-0606IGCTR")
      )
      (libsource (lib "eagle-import") (part "B38G3RGB"))
    )
    (comp (ref "LED109")
      (value "B38G3RGB")
      (footprint "eagle-import:B38G3RGB")
      (fields
        (field (name "ARROW_PART_NUMBER") "SML-LX0606IGC-TR")
        (field (name "MOUSER_PART_NUMBER") "696-SML-0606IGCTR")
      )
      (libsource (lib "eagle-import") (part "B38G3RGB"))
    )
    (comp (ref "LED110")
      (value "B38G3RGB")
      (footprint "eagle-import:B38G3RGB")
      (fields
        (field (name "ARROW_PART_NUMBER") "SML-LX0606IGC-TR")
        (field (name "MOUSER_PART_NUMBER") "696-SML-0606IGCTR")
      )
      (libsource (lib "eagle-import") (part "B38G3RGB"))
    )
    (comp (ref "LED111")
      (value "B38G3RGB")
      (footprint "eagle-import:B38G3RGB")
      (fields
        (field (name "ARROW_PART_NUMBER") "SML-LX0606IGC-TR")
        (field (name "MOUSER_PART_NUMBER") "696-SML-0606IGCTR")
      )
      (libsource (lib "eagle-import") (part "B38G3RGB"))
    )
    (comp (ref "LED112")
      (value "B38G3RGB")
      (footprint "eagle-import:B38G3RGB")
      (fields
        (field (name "ARROW_PART_NUMBER") "SML-LX0606IGC-TR")
        (field (name "MOUSER_PART_NUMBER") "696-SML-0606IGCTR")
      )
      (libsource (lib "eagle-import") (part "B38G3RGB"))
    )
    (comp (ref "LED113")
      (value "B38G3RGB")
      (footprint "eagle-import:B38G3RGB")
      (fields
        (field (name "ARROW_PART_NUMBER") "SML-LX0606IGC-TR")
        (field (name "MOUSER_PART_NUMBER") "696-SML-0606IGCTR")
      )
      (libsource (lib "eagle-import") (part "B38G3RGB"))
    )
    (comp (ref "LED114")
      (value "B38G3RGB")
      (footprint "eagle-import:B38G3RGB")
      (fields
        (field (name "ARROW_PART_NUMBER") "SML-LX0606IGC-TR")
        (field (name "MOUSER_PART_NUMBER") "696-SML-0606IGCTR")
      )
      (libsource (lib "eagle-import") (part "B38G3RGB"))
    )
    (comp (ref "LED115")
      (value "B38G3RGB")
      (footprint "eagle-import:B38G3RGB")
      (fields
        (field (name "ARROW_PART_NUMBER") "SML-LX0606IGC-TR")
        (field (name "MOUSER_PART_NUMBER") "696-SML-0606IGCTR")
      )
      (libsource (lib "eagle-import") (part "B38G3RGB"))
    )
    (comp (ref "LED116")
      (value "B38G3RGB")
      (footprint "eagle-import:B38G3RGB")
      (fields
        (field (name "ARROW_PART_NUMBER") "SML-LX0606IGC-TR")
        (field (name "MOUSER_PART_NUMBER") "696-SML-0606IGCTR")
      )
      (libsource (lib "eagle-import") (part "B38G3RGB"))
    )
    (comp (ref "LED117")
      (value "B38G3RGB")
      (footprint "eagle-import:B38G3RGB")
      (fields
        (field (name "ARROW_PART_NUMBER") "SML-LX0606IGC-TR")
        (field (name "MOUSER_PART_NUMBER") "696-SML-0606IGCTR")
      )
      (libsource (lib "eagle-import") (part "B38G3RGB"))
    )
    (comp (ref "LED118")
      (value "B38G3RGB")
      (footprint "eagle-import:B38G3RGB")
      (fields
        (field (name "ARROW_PART_NUMBER") "SML-LX0606IGC-TR")
        (field (name "MOUSER_PART_NUMBER") "696-SML-0606IGCTR")
      )
      (libsource (lib "eagle-import") (part "B38G3RGB"))
    )
    (comp (ref "LED119")
      (value "B38G3RGB")
      (footprint "eagle-import:B38G3RGB")
      (fields
        (field (name "ARROW_PART_NUMBER") "SML-LX0606IGC-TR")
        (field (name "MOUSER_PART_NUMBER") "696-SML-0606IGCTR")
      )
      (libsource (lib "eagle-import") (part "B38G3RGB"))
    )
    (comp (ref "LED120")
      (value "B38G3RGB")
      (footprint "eagle-import:B38G3RGB")
      (fields
        (field (name "ARROW_PART_NUMBER") "SML-LX0606IGC-TR")
        (field (name "MOUSER_PART_NUMBER") "696-SML-0606IGCTR")
      )
      (libsource (lib "eagle-import") (part "B38G3RGB"))
    )
    (comp (ref "SV1")
      (value "MA06-2")
      (footprint "eagle-import:MA06-2")
      (libsource (lib "eagle-import") (part "MA06-2"))
    )
  )
  (nets
    (net (code "1") (name "/3V3") (class "Default")
      (node (ref "C1") (pin "1") (pinfunction "1_1") (pintype "passive"))
      (node (ref "C2") (pin "1") (pinfunction "1_1") (pintype "passive"))
      (node (ref "C3") (pin "1") (pinfunction "1_1") (pintype "passive"))
      (node (ref "C4") (pin "1") (pinfunction "1_1") (pintype "passive"))
      (node (ref "C5") (pin "1") (pinfunction "1_1") (pintype "passive"))
      (node (ref "C6") (pin "1") (pinfunction "1_1") (pintype "passive"))
      (node (ref "C7") (pin "1") (pinfunction "1_1") (pintype "passive"))
      (node (ref "C8") (pin "1") (pinfunction "1_1") (pintype "passive"))
      (node (ref "C9") (pin "1") (pinfunction "1_1") (pintype "passive"))
      (node (ref "IC1") (pin "54") (pinfunction "VCC_54") (pintype "bidirectional"))
      (node (ref "IC2") (pin "54") (pinfunction "VCC_54") (pintype "bidirectional"))
      (node (ref "IC3") (pin "54") (pinfunction "VCC_54") (pintype "bidirectional"))
      (node (ref "IC4") (pin "54") (pinfunction "VCC_54") (pintype "bidirectional"))
      (node (ref "IC5") (pin "54") (pinfunction "VCC_54") (pintype "bidirectional"))
      (node (ref "IC6") (pin "54") (pinfunction "VCC_54") (pintype "bidirectional"))
      (node (ref "IC7") (pin "54") (pinfunction "VCC_54") (pintype "bidirectional"))
      (node (ref "IC8") (pin "54") (pinfunction "VCC_54") (pintype "bidirectional"))
      (node (ref "LED1") (pin "3") (pinfunction "COM_3") (pintype "bidirectional"))
      (node (ref "LED10") (pin "3") (pinfunction "COM_3") (pintype "bidirectional"))
      (node (ref "LED100") (pin "3") (pinfunction "COM_3") (pintype "bidirectional"))
      (node (ref "LED101") (pin "3") (pinfunction "COM_3") (pintype "bidirectional"))
      (node (ref "LED102") (pin "3") (pinfunction "COM_3") (pintype "bidirectional"))
      (node (ref "LED103") (pin "3") (pinfunction "COM_3") (pintype "bidirectional"))
      (node (ref "LED104") (pin "3") (pinfunction "COM_3") (pintype "bidirectional"))
      (node (ref "LED105") (pin "3") (pinfunction "COM_3") (pintype "bidirectional"))
      (node (ref "LED106") (pin "3") (pinfunction "COM_3") (pintype "bidirectional"))
      (node (ref "LED107") (pin "3") (pinfunction "COM_3") (pintype "bidirectional"))
      (node (ref "LED108") (pin "3") (pinfunction "COM_3") (pintype "bidirectional"))
      (node (ref "LED109") (pin "3") (pinfunction "COM_3") (pintype "bidirectional"))
      (node (ref "LED11") (pin "3") (pinfunction "COM_3") (pintype "bidirectional"))
      (node (ref "LED110") (pin "3") (pinfunction "COM_3") (pintype "bidirectional"))
      (node (ref "LED111") (pin "3") (pinfunction "COM_3") (pintype "bidirectional"))
      (node (ref "LED112") (pin "3") (pinfunction "COM_3") (pintype "bidirectional"))
      (node (ref "LED113") (pin "3") (pinfunction "COM_3") (pintype "bidirectional"))
      (node (ref "LED114") (pin "3") (pinfunction "COM_3") (pintype "bidirectional"))
      (node (ref "LED115") (pin "3") (pinfunction "COM_3") (pintype "bidirectional"))
      (node (ref "LED116") (pin "3") (pinfunction "COM_3") (pintype "bidirectional"))
      (node (ref "LED117") (pin "3") (pinfunction "COM_3") (pintype "bidirectional"))
      (node (ref "LED118") (pin "3") (pinfunction "COM_3") (pintype "bidirectional"))
      (node (ref "LED119") (pin "3") (pinfunction "COM_3") (pintype "bidirectional"))
      (node (ref "LED12") (pin "3") (pinfunction "COM_3") (pintype "bidirectional"))
      (node (ref "LED120") (pin "3") (pinfunction "COM_3") (pintype "bidirectional"))
      (node (ref "LED13") (pin "3") (pinfunction "COM_3") (pintype "bidirectional"))
      (node (ref "LED14") (pin "3") (pinfunction "COM_3") (pintype "bidirectional"))
      (node (ref "LED15") (pin "3") (pinfunction "COM_3") (pintype "bidirectional"))
      (node (ref "LED16") (pin "3") (pinfunction "COM_3") (pintype "bidirectional"))
      (node (ref "LED17") (pin "3") (pinfunction "COM_3") (pintype "bidirectional"))
      (node (ref "LED18") (pin "3") (pinfunction "COM_3") (pintype "bidirectional"))
      (node (ref "LED19") (pin "3") (pinfunction "COM_3") (pintype "bidirectional"))
      (node (ref "LED2") (pin "3") (pinfunction "COM_3") (pintype "bidirectional"))
      (node (ref "LED20") (pin "3") (pinfunction "COM_3") (pintype "bidirectional"))
      (node (ref "LED21") (pin "3") (pinfunction "COM_3") (pintype "bidirectional"))
      (node (ref "LED22") (pin "3") (pinfunction "COM_3") (pintype "bidirectional"))
      (node (ref "LED23") (pin "3") (pinfunction "COM_3") (pintype "bidirectional"))
      (node (ref "LED24") (pin "3") (pinfunction "COM_3") (pintype "bidirectional"))
      (node (ref "LED25") (pin "3") (pinfunction "COM_3") (pintype "bidirectional"))
      (node (ref "LED26") (pin "3") (pinfunction "COM_3") (pintype "bidirectional"))
      (node (ref "LED27") (pin "3") (pinfunction "COM_3") (pintype "bidirectional"))
      (node (ref "LED28") (pin "3") (pinfunction "COM_3") (pintype "bidirectional"))
      (node (ref "LED29") (pin "3") (pinfunction "COM_3") (pintype "bidirectional"))
      (node (ref "LED3") (pin "3") (pinfunction "COM_3") (pintype "bidirectional"))
      (node (ref "LED30") (pin "3") (pinfunction "COM_3") (pintype "bidirectional"))
      (node (ref "LED31") (pin "3") (pinfunction "COM_3") (pintype "bidirectional"))
      (node (ref "LED32") (pin "3") (pinfunction "COM_3") (pintype "bidirectional"))
      (node (ref "LED33") (pin "3") (pinfunction "COM_3") (pintype "bidirectional"))
      (node (ref "LED34") (pin "3") (pinfunction "COM_3") (pintype "bidirectional"))
      (node (ref "LED35") (pin "3") (pinfunction "COM_3") (pintype "bidirectional"))
      (node (ref "LED36") (pin "3") (pinfunction "COM_3") (pintype "bidirectional"))
      (node (ref "LED37") (pin "3") (pinfunction "COM_3") (pintype "bidirectional"))
      (node (ref "LED38") (pin "3") (pinfunction "COM_3") (pintype "bidirectional"))
      (node (ref "LED39") (pin "3") (pinfunction "COM_3") (pintype "bidirectional"))
      (node (ref "LED4") (pin "3") (pinfunction "COM_3") (pintype "bidirectional"))
      (node (ref "LED40") (pin "3") (pinfunction "COM_3") (pintype "bidirectional"))
      (node (ref "LED41") (pin "3") (pinfunction "COM_3") (pintype "bidirectional"))
      (node (ref "LED42") (pin "3") (pinfunction "COM_3") (pintype "bidirectional"))
      (node (ref "LED43") (pin "3") (pinfunction "COM_3") (pintype "bidirectional"))
      (node (ref "LED44") (pin "3") (pinfunction "COM_3") (pintype "bidirectional"))
      (node (ref "LED45") (pin "3") (pinfunction "COM_3") (pintype "bidirectional"))
      (node (ref "LED46") (pin "3") (pinfunction "COM_3") (pintype "bidirectional"))
      (node (ref "LED47") (pin "3") (pinfunction "COM_3") (pintype "bidirectional"))
      (node (ref "LED48") (pin "3") (pinfunction "COM_3") (pintype "bidirectional"))
      (node (ref "LED49") (pin "3") (pinfunction "COM_3") (pintype "bidirectional"))
      (node (ref "LED5") (pin "3") (pinfunction "COM_3") (pintype "bidirectional"))
      (node (ref "LED50") (pin "3") (pinfunction "COM_3") (pintype "bidirectional"))
      (node (ref "LED51") (pin "3") (pinfunction "COM_3") (pintype "bidirectional"))
      (node (ref "LED52") (pin "3") (pinfunction "COM_3") (pintype "bidirectional"))
      (node (ref "LED53") (pin "3") (pinfunction "COM_3") (pintype "bidirectional"))
      (node (ref "LED54") (pin "3") (pinfunction "COM_3") (pintype "bidirectional"))
      (node (ref "LED55") (pin "3") (pinfunction "COM_3") (pintype "bidirectional"))
      (node (ref "LED56") (pin "3") (pinfunction "COM_3") (pintype "bidirectional"))
      (node (ref "LED57") (pin "3") (pinfunction "COM_3") (pintype "bidirectional"))
      (node (ref "LED58") (pin "3") (pinfunction "COM_3") (pintype "bidirectional"))
      (node (ref "LED59") (pin "3") (pinfunction "COM_3") (pintype "bidirectional"))
      (node (ref "LED6") (pin "3") (pinfunction "COM_3") (pintype "bidirectional"))
      (node (ref "LED60") (pin "3") (pinfunction "COM_3") (pintype "bidirectional"))
      (node (ref "LED61") (pin "3") (pinfunction "COM_3") (pintype "bidirectional"))
      (node (ref "LED62") (pin "3") (pinfunction "COM_3") (pintype "bidirectional"))
      (node (ref "LED63") (pin "3") (pinfunction "COM_3") (pintype "bidirectional"))
      (node (ref "LED64") (pin "3") (pinfunction "COM_3") (pintype "bidirectional"))
      (node (ref "LED65") (pin "3") (pinfunction "COM_3") (pintype "bidirectional"))
      (node (ref "LED66") (pin "3") (pinfunction "COM_3") (pintype "bidirectional"))
      (node (ref "LED67") (pin "3") (pinfunction "COM_3") (pintype "bidirectional"))
      (node (ref "LED68") (pin "3") (pinfunction "COM_3") (pintype "bidirectional"))
      (node (ref "LED69") (pin "3") (pinfunction "COM_3") (pintype "bidirectional"))
      (node (ref "LED7") (pin "3") (pinfunction "COM_3") (pintype "bidirectional"))
      (node (ref "LED70") (pin "3") (pinfunction "COM_3") (pintype "bidirectional"))
      (node (ref "LED71") (pin "3") (pinfunction "COM_3") (pintype "bidirectional"))
      (node (ref "LED72") (pin "3") (pinfunction "COM_3") (pintype "bidirectional"))
      (node (ref "LED73") (pin "3") (pinfunction "COM_3") (pintype "bidirectional"))
      (node (ref "LED74") (pin "3") (pinfunction "COM_3") (pintype "bidirectional"))
      (node (ref "LED75") (pin "3") (pinfunction "COM_3") (pintype "bidirectional"))
      (node (ref "LED76") (pin "3") (pinfunction "COM_3") (pintype "bidirectional"))
      (node (ref "LED77") (pin "3") (pinfunction "COM_3") (pintype "bidirectional"))
      (node (ref "LED78") (pin "3") (pinfunction "COM_3") (pintype "bidirectional"))
      (node (ref "LED79") (pin "3") (pinfunction "COM_3") (pintype "bidirectional"))
      (node (ref "LED8") (pin "3") (pinfunction "COM_3") (pintype "bidirectional"))
      (node (ref "LED80") (pin "3") (pinfunction "COM_3") (pintype "bidirectional"))
      (node (ref "LED81") (pin "3") (pinfunction "COM_3") (pintype "bidirectional"))
      (node (ref "LED82") (pin "3") (pinfunction "COM_3") (pintype "bidirectional"))
      (node (ref "LED83") (pin "3") (pinfunction "COM_3") (pintype "bidirectional"))
      (node (ref "LED84") (pin "3") (pinfunction "COM_3") (pintype "bidirectional"))
      (node (ref "LED85") (pin "3") (pinfunction "COM_3") (pintype "bidirectional"))
      (node (ref "LED86") (pin "3") (pinfunction "COM_3") (pintype "bidirectional"))
      (node (ref "LED87") (pin "3") (pinfunction "COM_3") (pintype "bidirectional"))
      (node (ref "LED88") (pin "3") (pinfunction "COM_3") (pintype "bidirectional"))
      (node (ref "LED89") (pin "3") (pinfunction "COM_3") (pintype "bidirectional"))
      (node (ref "LED9") (pin "3") (pinfunction "COM_3") (pintype "bidirectional"))
      (node (ref "LED90") (pin "3") (pinfunction "COM_3") (pintype "bidirectional"))
      (node (ref "LED91") (pin "3") (pinfunction "COM_3") (pintype "bidirectional"))
      (node (ref "LED92") (pin "3") (pinfunction "COM_3") (pintype "bidirectional"))
      (node (ref "LED93") (pin "3") (pinfunction "COM_3") (pintype "bidirectional"))
      (node (ref "LED94") (pin "3") (pinfunction "COM_3") (pintype "bidirectional"))
      (node (ref "LED95") (pin "3") (pinfunction "COM_3") (pintype "bidirectional"))
      (node (ref "LED96") (pin "3") (pinfunction "COM_3") (pintype "bidirectional"))
      (node (ref "LED97") (pin "3") (pinfunction "COM_3") (pintype "bidirectional"))
      (node (ref "LED98") (pin "3") (pinfunction "COM_3") (pintype "bidirectional"))
      (node (ref "LED99") (pin "3") (pinfunction "COM_3") (pintype "bidirectional"))
      (node (ref "SV1") (pin "6") (pinfunction "6_6") (pintype "passive"))
      (node (ref "SV1") (pin "8") (pinfunction "8_8") (pintype "passive"))
    )
    (net (code "2") (name "/GND") (class "Default")
      (node (ref "C1") (pin "2") (pinfunction "2_2") (pintype "passive"))
      (node (ref "C2") (pin "2") (pinfunction "2_2") (pintype "passive"))
      (node (ref "C3") (pin "2") (pinfunction "2_2") (pintype "passive"))
      (node (ref "C4") (pin "2") (pinfunction "2_2") (pintype "passive"))
      (node (ref "C5") (pin "2") (pinfunction "2_2") (pintype "passive"))
      (node (ref "C6") (pin "2") (pinfunction "2_2") (pintype "passive"))
      (node (ref "C7") (pin "2") (pinfunction "2_2") (pintype "passive"))
      (node (ref "C8") (pin "2") (pinfunction "2_2") (pintype "passive"))
      (node (ref "C9") (pin "2") (pinfunction "2_2") (pintype "passive"))
      (node (ref "IC1") (pin "29") (pinfunction "GND_1_29") (pintype "bidirectional"))
      (node (ref "IC1") (pin "56") (pinfunction "GND_2_56") (pintype "bidirectional"))
      (node (ref "IC1") (pin "57") (pinfunction "THERMALPAD_57") (pintype "bidirectional"))
      (node (ref "IC2") (pin "29") (pinfunction "GND_1_29") (pintype "bidirectional"))
      (node (ref "IC2") (pin "56") (pinfunction "GND_2_56") (pintype "bidirectional"))
      (node (ref "IC2") (pin "57") (pinfunction "THERMALPAD_57") (pintype "bidirectional"))
      (node (ref "IC3") (pin "29") (pinfunction "GND_1_29") (pintype "bidirectional"))
      (node (ref "IC3") (pin "56") (pinfunction "GND_2_56") (pintype "bidirectional"))
      (node (ref "IC3") (pin "57") (pinfunction "THERMALPAD_57") (pintype "bidirectional"))
      (node (ref "IC4") (pin "29") (pinfunction "GND_1_29") (pintype "bidirectional"))
      (node (ref "IC4") (pin "56") (pinfunction "GND_2_56") (pintype "bidirectional"))
      (node (ref "IC4") (pin "57") (pinfunction "THERMALPAD_57") (pintype "bidirectional"))
      (node (ref "IC5") (pin "29") (pinfunction "GND_1_29") (pintype "bidirectional"))
      (node (ref "IC5") (pin "56") (pinfunction "GND_2_56") (pintype "bidirectional"))
      (node (ref "IC5") (pin "57") (pinfunction "THERMALPAD_57") (pintype "bidirectional"))
      (node (ref "IC6") (pin "29") (pinfunction "GND_1_29") (pintype "bidirectional"))
      (node (ref "IC6") (pin "56") (pinfunction "GND_2_56") (pintype "bidirectional"))
      (node (ref "IC6") (pin "57") (pinfunction "THERMALPAD_57") (pintype "bidirectional"))
      (node (ref "IC7") (pin "29") (pinfunction "GND_1_29") (pintype "bidirectional"))
      (node (ref "IC7") (pin "56") (pinfunction "GND_2_56") (pintype "bidirectional"))
      (node (ref "IC7") (pin "57") (pinfunction "THERMALPAD_57") (pintype "bidirectional"))
      (node (ref "IC8") (pin "29") (pinfunction "GND_1_29") (pintype "bidirectional"))
      (node (ref "IC8") (pin "56") (pinfunction "GND_2_56") (pintype "bidirectional"))
      (node (ref "IC8") (pin "57") (pinfunction "THERMALPAD_57") (pintype "bidirectional"))
      (node (ref "SV1") (pin "10") (pinfunction "10_10") (pintype "passive"))
      (node (ref "SV1") (pin "12") (pinfunction "12_12") (pintype "passive"))
      (node (ref "SV1") (pin "9") (pinfunction "9_9") (pintype "passive"))
    )
    (net (code "3") (name "/GSCLK") (class "Default")
      (node (ref "IC1") (pin "55") (pinfunction "GSCLK_55") (pintype "bidirectional"))
      (node (ref "IC2") (pin "55") (pinfunction "GSCLK_55") (pintype "bidirectional"))
      (node (ref "IC3") (pin "55") (pinfunction "GSCLK_55") (pintype "bidirectional"))
      (node (ref "IC4") (pin "55") (pinfunction "GSCLK_55") (pintype "bidirectional"))
      (node (ref "IC5") (pin "55") (pinfunction "GSCLK_55") (pintype "bidirectional"))
      (node (ref "IC6") (pin "55") (pinfunction "GSCLK_55") (pintype "bidirectional"))
      (node (ref "IC7") (pin "55") (pinfunction "GSCLK_55") (pintype "bidirectional"))
      (node (ref "IC8") (pin "55") (pinfunction "GSCLK_55") (pintype "bidirectional"))
      (node (ref "SV1") (pin "11") (pinfunction "11_11") (pintype "passive"))
    )
    (net (code "4") (name "/LAT") (class "Default")
      (node (ref "IC1") (pin "3") (pinfunction "LAT_3") (pintype "bidirectional"))
      (node (ref "IC2") (pin "3") (pinfunction "LAT_3") (pintype "bidirectional"))
      (node (ref "IC3") (pin "3") (pinfunction "LAT_3") (pintype "bidirectional"))
      (node (ref "IC4") (pin "3") (pinfunction "LAT_3") (pintype "bidirectional"))
      (node (ref "IC5") (pin "3") (pinfunction "LAT_3") (pintype "bidirectional"))
      (node (ref "IC6") (pin "3") (pinfunction "LAT_3") (pintype "bidirectional"))
      (node (ref "IC7") (pin "3") (pinfunction "LAT_3") (pintype "bidirectional"))
      (node (ref "IC8") (pin "3") (pinfunction "LAT_3") (pintype "bidirectional"))
      (node (ref "SV1") (pin "5") (pinfunction "5_5") (pintype "passive"))
    )
    (net (code "5") (name "/N$352") (class "Default")
      (node (ref "IC8") (pin "53") (pinfunction "OUTB8_53") (pintype "bidirectional"))
    )
    (net (code "6") (name "/N$353") (class "Default")
      (node (ref "IC8") (pin "52") (pinfunction "OUTR8_52") (pintype "bidirectional"))
    )
    (net (code "7") (name "/N$354") (class "Default")
      (node (ref "IC8") (pin "51") (pinfunction "OUTG8_51") (pintype "bidirectional"))
    )
    (net (code "8") (name "/N$355") (class "Default")
      (node (ref "IC8") (pin "50") (pinfunction "OUTB12_50") (pintype "bidirectional"))
    )
    (net (code "9") (name "/N$356") (class "Default")
      (node (ref "IC8") (pin "49") (pinfunction "OUTR12_49") (pintype "bidirectional"))
    )
    (net (code "10") (name "/N$357") (class "Default")
      (node (ref "IC8") (pin "48") (pinfunction "OUTG12_48") (pintype "bidirectional"))
    )
    (net (code "11") (name "/N$358") (class "Default")
      (node (ref "IC8") (pin "47") (pinfunction "OUTB9_47") (pintype "bidirectional"))
    )
    (net (code "12") (name "/N$359") (class "Default")
      (node (ref "IC8") (pin "46") (pinfunction "OUTR9_46") (pintype "bidirectional"))
    )
    (net (code "13") (name "/N$360") (class "Default")
      (node (ref "IC8") (pin "45") (pinfunction "OUTG9_45") (pintype "bidirectional"))
    )
    (net (code "14") (name "/N$361") (class "Default")
      (node (ref "IC8") (pin "44") (pinfunction "OUTB13_44") (pintype "bidirectional"))
    )
    (net (code "15") (name "/N$362") (class "Default")
      (node (ref "IC8") (pin "43") (pinfunction "OUTR13_43") (pintype "bidirectional"))
    )
    (net (code "16") (name "/N$363") (class "Default")
      (node (ref "IC8") (pin "42") (pinfunction "OUTG13_42") (pintype "bidirectional"))
    )
    (net (code "17") (name "/N$IC8_PIN4") (class "Default")
      (node (ref "IC8") (pin "4") (pinfunction "OUTB4_4") (pintype "bidirectional"))
    )
    (net (code "18") (name "/N$IC8_PIN5") (class "Default")
      (node (ref "IC8") (pin "5") (pinfunction "OUTR4_5") (pintype "bidirectional"))
    )
    (net (code "19") (name "/N$IC8_PIN6") (class "Default")
      (node (ref "IC8") (pin "6") (pinfunction "OUTG4_6") (pintype "bidirectional"))
    )
    (net (code "20") (name "/N$IC8_PIN7") (class "Default")
      (node (ref "IC8") (pin "7") (pinfunction "OUTB0_7") (pintype "bidirectional"))
    )
    (net (code "21") (name "/N$IC8_PIN8") (class "Default")
      (node (ref "IC8") (pin "8") (pinfunction "OUTR0_8") (pintype "bidirectional"))
    )
    (net (code "22") (name "/N$IC8_PIN9") (class "Default")
      (node (ref "IC8") (pin "9") (pinfunction "OUTG0_9") (pintype "bidirectional"))
    )
    (net (code "23") (name "/N$IC8_PIN10") (class "Default")
      (node (ref "IC8") (pin "10") (pinfunction "OUTB5_10") (pintype "bidirectional"))
    )
    (net (code "24") (name "/N$IC8_PIN11") (class "Default")
      (node (ref "IC8") (pin "11") (pinfunction "OUTR5_11") (pintype "bidirectional"))
    )
    (net (code "25") (name "/N$IC8_PIN12") (class "Default")
      (node (ref "IC8") (pin "12") (pinfunction "OUTG5_12") (pintype "bidirectional"))
    )
    (net (code "26") (name "/N$IC8_PIN13") (class "Default")
      (node (ref "IC8") (pin "13") (pinfunction "OUTB1_13") (pintype "bidirectional"))
    )
    (net (code "27") (name "/N$IC8_PIN14") (class "Default")
      (node (ref "IC8") (pin "14") (pinfunction "OUTR1_14") (pintype "bidirectional"))
    )
    (net (code "28") (name "/N$IC8_PIN15") (class "Default")
      (node (ref "IC8") (pin "15") (pinfunction "OUTG1_15") (pintype "bidirectional"))
    )
    (net (code "29") (name "/N$LEDB1") (class "Default")
      (node (ref "IC1") (pin "25") (pinfunction "OUTB7_25") (pintype "bidirectional"))
      (node (ref "LED1") (pin "2") (pinfunction "BLUE_2") (pintype "bidirectional"))
    )
    (net (code "30") (name "/N$LEDB2") (class "Default")
      (node (ref "IC1") (pin "22") (pinfunction "OUTB3_22") (pintype "bidirectional"))
      (node (ref "LED2") (pin "2") (pinfunction "BLUE_2") (pintype "bidirectional"))
    )
    (net (code "31") (name "/N$LEDB3") (class "Default")
      (node (ref "IC1") (pin "32") (pinfunction "OUTB11_32") (pintype "bidirectional"))
      (node (ref "LED3") (pin "2") (pinfunction "BLUE_2") (pintype "bidirectional"))
    )
    (net (code "32") (name "/N$LEDB4") (class "Default")
      (node (ref "IC1") (pin "35") (pinfunction "OUTB15_35") (pintype "bidirectional"))
      (node (ref "LED4") (pin "2") (pinfunction "BLUE_2") (pintype "bidirectional"))
    )
    (net (code "33") (name "/N$LEDB5") (class "Default")
      (node (ref "IC1") (pin "19") (pinfunction "OUTB6_19") (pintype "bidirectional"))
      (node (ref "LED5") (pin "2") (pinfunction "BLUE_2") (pintype "bidirectional"))
    )
    (net (code "34") (name "/N$LEDB6") (class "Default")
      (node (ref "IC1") (pin "16") (pinfunction "OUTB2_16") (pintype "bidirectional"))
      (node (ref "LED6") (pin "2") (pinfunction "BLUE_2") (pintype "bidirectional"))
    )
    (net (code "35") (name "/N$LEDB7") (class "Default")
      (node (ref "IC1") (pin "38") (pinfunction "OUTB10_38") (pintype "bidirectional"))
      (node (ref "LED7") (pin "2") (pinfunction "BLUE_2") (pintype "bidirectional"))
    )
    (net (code "36") (name "/N$LEDB8") (class "Default")
      (node (ref "IC1") (pin "41") (pinfunction "OUTB14_41") (pintype "bidirectional"))
      (node (ref "LED8") (pin "2") (pinfunction "BLUE_2") (pintype "bidirectional"))
    )
    (net (code "37") (name "/N$LEDB9") (class "Default")
      (node (ref "IC1") (pin "13") (pinfunction "OUTB1_13") (pintype "bidirectional"))
      (node (ref "LED9") (pin "2") (pinfunction "BLUE_2") (pintype "bidirectional"))
    )
    (net (code "38") (name "/N$LEDB10") (class "Default")
      (node (ref "IC1") (pin "10") (pinfunction "OUTB5_10") (pintype "bidirectional"))
      (node (ref "LED10") (pin "2") (pinfunction "BLUE_2") (pintype "bidirectional"))
    )
    (net (code "39") (name "/N$LEDB11") (class "Default")
      (node (ref "IC1") (pin "44") (pinfunction "OUTB13_44") (pintype "bidirectional"))
      (node (ref "LED11") (pin "2") (pinfunction "BLUE_2") (pintype "bidirectional"))
    )
    (net (code "40") (name "/N$LEDB12") (class "Default")
      (node (ref "IC1") (pin "47") (pinfunction "OUTB9_47") (pintype "bidirectional"))
      (node (ref "LED12") (pin "2") (pinfunction "BLUE_2") (pintype "bidirectional"))
    )
    (net (code "41") (name "/N$LEDB13") (class "Default")
      (node (ref "IC1") (pin "4") (pinfunction "OUTB4_4") (pintype "bidirectional"))
      (node (ref "LED13") (pin "2") (pinfunction "BLUE_2") (pintype "bidirectional"))
    )
    (net (code "42") (name "/N$LEDB14") (class "Default")
      (node (ref "IC1") (pin "7") (pinfunction "OUTB0_7") (pintype "bidirectional"))
      (node (ref "LED14") (pin "2") (pinfunction "BLUE_2") (pintype "bidirectional"))
    )
    (net (code "43") (name "/N$LEDB15") (class "Default")
      (node (ref "IC1") (pin "50") (pinfunction "OUTB12_50") (pintype "bidirectional"))
      (node (ref "LED15") (pin "2") (pinfunction "BLUE_2") (pintype "bidirectional"))
    )
    (net (code "44") (name "/N$LEDB16") (class "Default")
      (node (ref "IC1") (pin "53") (pinfunction "OUTB8_53") (pintype "bidirectional"))
      (node (ref "LED16") (pin "2") (pinfunction "BLUE_2") (pintype "bidirectional"))
    )
    (net (code "45") (name "/N$LEDB17") (class "Default")
      (node (ref "IC2") (pin "25") (pinfunction "OUTB7_25") (pintype "bidirectional"))
      (node (ref "LED17") (pin "2") (pinfunction "BLUE_2") (pintype "bidirectional"))
    )
    (net (code "46") (name "/N$LEDB18") (class "Default")
      (node (ref "IC2") (pin "22") (pinfunction "OUTB3_22") (pintype "bidirectional"))
      (node (ref "LED18") (pin "2") (pinfunction "BLUE_2") (pintype "bidirectional"))
    )
    (net (code "47") (name "/N$LEDB19") (class "Default")
      (node (ref "IC2") (pin "32") (pinfunction "OUTB11_32") (pintype "bidirectional"))
      (node (ref "LED19") (pin "2") (pinfunction "BLUE_2") (pintype "bidirectional"))
    )
    (net (code "48") (name "/N$LEDB20") (class "Default")
      (node (ref "IC2") (pin "35") (pinfunction "OUTB15_35") (pintype "bidirectional"))
      (node (ref "LED20") (pin "2") (pinfunction "BLUE_2") (pintype "bidirectional"))
    )
    (net (code "49") (name "/N$LEDB21") (class "Default")
      (node (ref "IC2") (pin "19") (pinfunction "OUTB6_19") (pintype "bidirectional"))
      (node (ref "LED21") (pin "2") (pinfunction "BLUE_2") (pintype "bidirectional"))
    )
    (net (code "50") (name "/N$LEDB22") (class "Default")
      (node (ref "IC2") (pin "16") (pinfunction "OUTB2_16") (pintype "bidirectional"))
      (node (ref "LED22") (pin "2") (pinfunction "BLUE_2") (pintype "bidirectional"))
    )
    (net (code "51") (name "/N$LEDB23") (class "Default")
      (node (ref "IC2") (pin "38") (pinfunction "OUTB10_38") (pintype "bidirectional"))
      (node (ref "LED23") (pin "2") (pinfunction "BLUE_2") (pintype "bidirectional"))
    )
    (net (code "52") (name "/N$LEDB24") (class "Default")
      (node (ref "IC2") (pin "41") (pinfunction "OUTB14_41") (pintype "bidirectional"))
      (node (ref "LED24") (pin "2") (pinfunction "BLUE_2") (pintype "bidirectional"))
    )
    (net (code "53") (name "/N$LEDB25") (class "Default")
      (node (ref "IC2") (pin "13") (pinfunction "OUTB1_13") (pintype "bidirectional"))
      (node (ref "LED25") (pin "2") (pinfunction "BLUE_2") (pintype "bidirectional"))
    )
    (net (code "54") (name "/N$LEDB26") (class "Default")
      (node (ref "IC2") (pin "10") (pinfunction "OUTB5_10") (pintype "bidirectional"))
      (node (ref "LED26") (pin "2") (pinfunction "BLUE_2") (pintype "bidirectional"))
    )
    (net (code "55") (name "/N$LEDB27") (class "Default")
      (node (ref "IC2") (pin "44") (pinfunction "OUTB13_44") (pintype "bidirectional"))
      (node (ref "LED27") (pin "2") (pinfunction "BLUE_2") (pintype "bidirectional"))
    )
    (net (code "56") (name "/N$LEDB28") (class "Default")
      (node (ref "IC2") (pin "47") (pinfunction "OUTB9_47") (pintype "bidirectional"))
      (node (ref "LED28") (pin "2") (pinfunction "BLUE_2") (pintype "bidirectional"))
    )
    (net (code "57") (name "/N$LEDB29") (class "Default")
      (node (ref "IC2") (pin "4") (pinfunction "OUTB4_4") (pintype "bidirectional"))
      (node (ref "LED29") (pin "2") (pinfunction "BLUE_2") (pintype "bidirectional"))
    )
    (net (code "58") (name "/N$LEDB30") (class "Default")
      (node (ref "IC2") (pin "7") (pinfunction "OUTB0_7") (pintype "bidirectional"))
      (node (ref "LED30") (pin "2") (pinfunction "BLUE_2") (pintype "bidirectional"))
    )
    (net (code "59") (name "/N$LEDB31") (class "Default")
      (node (ref "IC2") (pin "50") (pinfunction "OUTB12_50") (pintype "bidirectional"))
      (node (ref "LED31") (pin "2") (pinfunction "BLUE_2") (pintype "bidirectional"))
    )
    (net (code "60") (name "/N$LEDB32") (class "Default")
      (node (ref "IC2") (pin "53") (pinfunction "OUTB8_53") (pintype "bidirectional"))
      (node (ref "LED32") (pin "2") (pinfunction "BLUE_2") (pintype "bidirectional"))
    )
    (net (code "61") (name "/N$LEDB33") (class "Default")
      (node (ref "IC3") (pin "25") (pinfunction "OUTB7_25") (pintype "bidirectional"))
      (node (ref "LED33") (pin "2") (pinfunction "BLUE_2") (pintype "bidirectional"))
    )
    (net (code "62") (name "/N$LEDB34") (class "Default")
      (node (ref "IC3") (pin "22") (pinfunction "OUTB3_22") (pintype "bidirectional"))
      (node (ref "LED34") (pin "2") (pinfunction "BLUE_2") (pintype "bidirectional"))
    )
    (net (code "63") (name "/N$LEDB35") (class "Default")
      (node (ref "IC3") (pin "32") (pinfunction "OUTB11_32") (pintype "bidirectional"))
      (node (ref "LED35") (pin "2") (pinfunction "BLUE_2") (pintype "bidirectional"))
    )
    (net (code "64") (name "/N$LEDB36") (class "Default")
      (node (ref "IC3") (pin "35") (pinfunction "OUTB15_35") (pintype "bidirectional"))
      (node (ref "LED36") (pin "2") (pinfunction "BLUE_2") (pintype "bidirectional"))
    )
    (net (code "65") (name "/N$LEDB37") (class "Default")
      (node (ref "IC3") (pin "19") (pinfunction "OUTB6_19") (pintype "bidirectional"))
      (node (ref "LED37") (pin "2") (pinfunction "BLUE_2") (pintype "bidirectional"))
    )
    (net (code "66") (name "/N$LEDB38") (class "Default")
      (node (ref "IC3") (pin "16") (pinfunction "OUTB2_16") (pintype "bidirectional"))
      (node (ref "LED38") (pin "2") (pinfunction "BLUE_2") (pintype "bidirectional"))
    )
    (net (code "67") (name "/N$LEDB39") (class "Default")
      (node (ref "IC3") (pin "38") (pinfunction "OUTB10_38") (pintype "bidirectional"))
      (node (ref "LED39") (pin "2") (pinfunction "BLUE_2") (pintype "bidirectional"))
    )
    (net (code "68") (name "/N$LEDB40") (class "Default")
      (node (ref "IC3") (pin "41") (pinfunction "OUTB14_41") (pintype "bidirectional"))
      (node (ref "LED40") (pin "2") (pinfunction "BLUE_2") (pintype "bidirectional"))
    )
    (net (code "69") (name "/N$LEDB41") (class "Default")
      (node (ref "IC3") (pin "13") (pinfunction "OUTB1_13") (pintype "bidirectional"))
      (node (ref "LED41") (pin "2") (pinfunction "BLUE_2") (pintype "bidirectional"))
    )
    (net (code "70") (name "/N$LEDB42") (class "Default")
      (node (ref "IC3") (pin "10") (pinfunction "OUTB5_10") (pintype "bidirectional"))
      (node (ref "LED42") (pin "2") (pinfunction "BLUE_2") (pintype "bidirectional"))
    )
    (net (code "71") (name "/N$LEDB43") (class "Default")
      (node (ref "IC3") (pin "44") (pinfunction "OUTB13_44") (pintype "bidirectional"))
      (node (ref "LED43") (pin "2") (pinfunction "BLUE_2") (pintype "bidirectional"))
    )
    (net (code "72") (name "/N$LEDB44") (class "Default")
      (node (ref "IC3") (pin "47") (pinfunction "OUTB9_47") (pintype "bidirectional"))
      (node (ref "LED44") (pin "2") (pinfunction "BLUE_2") (pintype "bidirectional"))
    )
    (net (code "73") (name "/N$LEDB45") (class "Default")
      (node (ref "IC3") (pin "4") (pinfunction "OUTB4_4") (pintype "bidirectional"))
      (node (ref "LED45") (pin "2") (pinfunction "BLUE_2") (pintype "bidirectional"))
    )
    (net (code "74") (name "/N$LEDB46") (class "Default")
      (node (ref "IC3") (pin "7") (pinfunction "OUTB0_7") (pintype "bidirectional"))
      (node (ref "LED46") (pin "2") (pinfunction "BLUE_2") (pintype "bidirectional"))
    )
    (net (code "75") (name "/N$LEDB47") (class "Default")
      (node (ref "IC3") (pin "50") (pinfunction "OUTB12_50") (pintype "bidirectional"))
      (node (ref "LED47") (pin "2") (pinfunction "BLUE_2") (pintype "bidirectional"))
    )
    (net (code "76") (name "/N$LEDB48") (class "Default")
      (node (ref "IC3") (pin "53") (pinfunction "OUTB8_53") (pintype "bidirectional"))
      (node (ref "LED48") (pin "2") (pinfunction "BLUE_2") (pintype "bidirectional"))
    )
    (net (code "77") (name "/N$LEDB49") (class "Default")
      (node (ref "IC4") (pin "25") (pinfunction "OUTB7_25") (pintype "bidirectional"))
      (node (ref "LED49") (pin "2") (pinfunction "BLUE_2") (pintype "bidirectional"))
    )
    (net (code "78") (name "/N$LEDB50") (class "Default")
      (node (ref "IC4") (pin "22") (pinfunction "OUTB3_22") (pintype "bidirectional"))
      (node (ref "LED50") (pin "2") (pinfunction "BLUE_2") (pintype "bidirectional"))
    )
    (net (code "79") (name "/N$LEDB51") (class "Default")
      (node (ref "IC4") (pin "32") (pinfunction "OUTB11_32") (pintype "bidirectional"))
      (node (ref "LED51") (pin "2") (pinfunction "BLUE_2") (pintype "bidirectional"))
    )
    (net (code "80") (name "/N$LEDB52") (class "Default")
      (node (ref "IC4") (pin "35") (pinfunction "OUTB15_35") (pintype "bidirectional"))
      (node (ref "LED52") (pin "2") (pinfunction "BLUE_2") (pintype "bidirectional"))
    )
    (net (code "81") (name "/N$LEDB53") (class "Default")
      (node (ref "IC4") (pin "19") (pinfunction "OUTB6_19") (pintype "bidirectional"))
      (node (ref "LED53") (pin "2") (pinfunction "BLUE_2") (pintype "bidirectional"))
    )
    (net (code "82") (name "/N$LEDB54") (class "Default")
      (node (ref "IC4") (pin "16") (pinfunction "OUTB2_16") (pintype "bidirectional"))
      (node (ref "LED54") (pin "2") (pinfunction "BLUE_2") (pintype "bidirectional"))
    )
    (net (code "83") (name "/N$LEDB55") (class "Default")
      (node (ref "IC4") (pin "38") (pinfunction "OUTB10_38") (pintype "bidirectional"))
      (node (ref "LED55") (pin "2") (pinfunction "BLUE_2") (pintype "bidirectional"))
    )
    (net (code "84") (name "/N$LEDB56") (class "Default")
      (node (ref "IC4") (pin "41") (pinfunction "OUTB14_41") (pintype "bidirectional"))
      (node (ref "LED56") (pin "2") (pinfunction "BLUE_2") (pintype "bidirectional"))
    )
    (net (code "85") (name "/N$LEDB57") (class "Default")
      (node (ref "IC4") (pin "13") (pinfunction "OUTB1_13") (pintype "bidirectional"))
      (node (ref "LED57") (pin "2") (pinfunction "BLUE_2") (pintype "bidirectional"))
    )
    (net (code "86") (name "/N$LEDB58") (class "Default")
      (node (ref "IC4") (pin "10") (pinfunction "OUTB5_10") (pintype "bidirectional"))
      (node (ref "LED58") (pin "2") (pinfunction "BLUE_2") (pintype "bidirectional"))
    )
    (net (code "87") (name "/N$LEDB59") (class "Default")
      (node (ref "IC4") (pin "44") (pinfunction "OUTB13_44") (pintype "bidirectional"))
      (node (ref "LED59") (pin "2") (pinfunction "BLUE_2") (pintype "bidirectional"))
    )
    (net (code "88") (name "/N$LEDB60") (class "Default")
      (node (ref "IC4") (pin "47") (pinfunction "OUTB9_47") (pintype "bidirectional"))
      (node (ref "LED60") (pin "2") (pinfunction "BLUE_2") (pintype "bidirectional"))
    )
    (net (code "89") (name "/N$LEDB61") (class "Default")
      (node (ref "IC4") (pin "4") (pinfunction "OUTB4_4") (pintype "bidirectional"))
      (node (ref "LED61") (pin "2") (pinfunction "BLUE_2") (pintype "bidirectional"))
    )
    (net (code "90") (name "/N$LEDB62") (class "Default")
      (node (ref "IC4") (pin "7") (pinfunction "OUTB0_7") (pintype "bidirectional"))
      (node (ref "LED62") (pin "2") (pinfunction "BLUE_2") (pintype "bidirectional"))
    )
    (net (code "91") (name "/N$LEDB63") (class "Default")
      (node (ref "IC4") (pin "50") (pinfunction "OUTB12_50") (pintype "bidirectional"))
      (node (ref "LED63") (pin "2") (pinfunction "BLUE_2") (pintype "bidirectional"))
    )
    (net (code "92") (name "/N$LEDB64") (class "Default")
      (node (ref "IC4") (pin "53") (pinfunction "OUTB8_53") (pintype "bidirectional"))
      (node (ref "LED64") (pin "2") (pinfunction "BLUE_2") (pintype "bidirectional"))
    )
    (net (code "93") (name "/N$LEDB65") (class "Default")
      (node (ref "IC5") (pin "25") (pinfunction "OUTB7_25") (pintype "bidirectional"))
      (node (ref "LED65") (pin "2") (pinfunction "BLUE_2") (pintype "bidirectional"))
    )
    (net (code "94") (name "/N$LEDB66") (class "Default")
      (node (ref "IC5") (pin "22") (pinfunction "OUTB3_22") (pintype "bidirectional"))
      (node (ref "LED66") (pin "2") (pinfunction "BLUE_2") (pintype "bidirectional"))
    )
    (net (code "95") (name "/N$LEDB67") (class "Default")
      (node (ref "IC5") (pin "32") (pinfunction "OUTB11_32") (pintype "bidirectional"))
      (node (ref "LED67") (pin "2") (pinfunction "BLUE_2") (pintype "bidirectional"))
    )
    (net (code "96") (name "/N$LEDB68") (class "Default")
      (node (ref "IC5") (pin "35") (pinfunction "OUTB15_35") (pintype "bidirectional"))
      (node (ref "LED68") (pin "2") (pinfunction "BLUE_2") (pintype "bidirectional"))
    )
    (net (code "97") (name "/N$LEDB69") (class "Default")
      (node (ref "IC5") (pin "19") (pinfunction "OUTB6_19") (pintype "bidirectional"))
      (node (ref "LED69") (pin "2") (pinfunction "BLUE_2") (pintype "bidirectional"))
    )
    (net (code "98") (name "/N$LEDB70") (class "Default")
      (node (ref "IC5") (pin "16") (pinfunction "OUTB2_16") (pintype "bidirectional"))
      (node (ref "LED70") (pin "2") (pinfunction "BLUE_2") (pintype "bidirectional"))
    )
    (net (code "99") (name "/N$LEDB71") (class "Default")
      (node (ref "IC5") (pin "38") (pinfunction "OUTB10_38") (pintype "bidirectional"))
      (node (ref "LED71") (pin "2") (pinfunction "BLUE_2") (pintype "bidirectional"))
    )
    (net (code "100") (name "/N$LEDB72") (class "Default")
      (node (ref "IC5") (pin "41") (pinfunction "OUTB14_41") (pintype "bidirectional"))
      (node (ref "LED72") (pin "2") (pinfunction "BLUE_2") (pintype "bidirectional"))
    )
    (net (code "101") (name "/N$LEDB73") (class "Default")
      (node (ref "IC5") (pin "13") (pinfunction "OUTB1_13") (pintype "bidirectional"))
      (node (ref "LED73") (pin "2") (pinfunction "BLUE_2") (pintype "bidirectional"))
    )
    (net (code "102") (name "/N$LEDB74") (class "Default")
      (node (ref "IC5") (pin "10") (pinfunction "OUTB5_10") (pintype "bidirectional"))
      (node (ref "LED74") (pin "2") (pinfunction "BLUE_2") (pintype "bidirectional"))
    )
    (net (code "103") (name "/N$LEDB75") (class "Default")
      (node (ref "IC5") (pin "44") (pinfunction "OUTB13_44") (pintype "bidirectional"))
      (node (ref "LED75") (pin "2") (pinfunction "BLUE_2") (pintype "bidirectional"))
    )
    (net (code "104") (name "/N$LEDB76") (class "Default")
      (node (ref "IC5") (pin "47") (pinfunction "OUTB9_47") (pintype "bidirectional"))
      (node (ref "LED76") (pin "2") (pinfunction "BLUE_2") (pintype "bidirectional"))
    )
    (net (code "105") (name "/N$LEDB77") (class "Default")
      (node (ref "IC5") (pin "4") (pinfunction "OUTB4_4") (pintype "bidirectional"))
      (node (ref "LED77") (pin "2") (pinfunction "BLUE_2") (pintype "bidirectional"))
    )
    (net (code "106") (name "/N$LEDB78") (class "Default")
      (node (ref "IC5") (pin "7") (pinfunction "OUTB0_7") (pintype "bidirectional"))
      (node (ref "LED78") (pin "2") (pinfunction "BLUE_2") (pintype "bidirectional"))
    )
    (net (code "107") (name "/N$LEDB79") (class "Default")
      (node (ref "IC5") (pin "50") (pinfunction "OUTB12_50") (pintype "bidirectional"))
      (node (ref "LED79") (pin "2") (pinfunction "BLUE_2") (pintype "bidirectional"))
    )
    (net (code "108") (name "/N$LEDB80") (class "Default")
      (node (ref "IC5") (pin "53") (pinfunction "OUTB8_53") (pintype "bidirectional"))
      (node (ref "LED80") (pin "2") (pinfunction "BLUE_2") (pintype "bidirectional"))
    )
    (net (code "109") (name "/N$LEDB81") (class "Default")
      (node (ref "IC6") (pin "25") (pinfunction "OUTB7_25") (pintype "bidirectional"))
      (node (ref "LED81") (pin "2") (pinfunction "BLUE_2") (pintype "bidirectional"))
    )
    (net (code "110") (name "/N$LEDB82") (class "Default")
      (node (ref "IC6") (pin "22") (pinfunction "OUTB3_22") (pintype "bidirectional"))
      (node (ref "LED82") (pin "2") (pinfunction "BLUE_2") (pintype "bidirectional"))
    )
    (net (code "111") (name "/N$LEDB83") (class "Default")
      (node (ref "IC6") (pin "32") (pinfunction "OUTB11_32") (pintype "bidirectional"))
      (node (ref "LED83") (pin "2") (pinfunction "BLUE_2") (pintype "bidirectional"))
    )
    (net (code "112") (name "/N$LEDB84") (class "Default")
      (node (ref "IC6") (pin "35") (pinfunction "OUTB15_35") (pintype "bidirectional"))
      (node (ref "LED84") (pin "2") (pinfunction "BLUE_2") (pintype "bidirectional"))
    )
    (net (code "113") (name "/N$LEDB85") (class "Default")
      (node (ref "IC6") (pin "19") (pinfunction "OUTB6_19") (pintype "bidirectional"))
      (node (ref "LED85") (pin "2") (pinfunction "BLUE_2") (pintype "bidirectional"))
    )
    (net (code "114") (name "/N$LEDB86") (class "Default")
      (node (ref "IC6") (pin "16") (pinfunction "OUTB2_16") (pintype "bidirectional"))
      (node (ref "LED86") (pin "2") (pinfunction "BLUE_2") (pintype "bidirectional"))
    )
    (net (code "115") (name "/N$LEDB87") (class "Default")
      (node (ref "IC6") (pin "38") (pinfunction "OUTB10_38") (pintype "bidirectional"))
      (node (ref "LED87") (pin "2") (pinfunction "BLUE_2") (pintype "bidirectional"))
    )
    (net (code "116") (name "/N$LEDB88") (class "Default")
      (node (ref "IC6") (pin "41") (pinfunction "OUTB14_41") (pintype "bidirectional"))
      (node (ref "LED88") (pin "2") (pinfunction "BLUE_2") (pintype "bidirectional"))
    )
    (net (code "117") (name "/N$LEDB89") (class "Default")
      (node (ref "IC6") (pin "13") (pinfunction "OUTB1_13") (pintype "bidirectional"))
      (node (ref "LED89") (pin "2") (pinfunction "BLUE_2") (pintype "bidirectional"))
    )
    (net (code "118") (name "/N$LEDB90") (class "Default")
      (node (ref "IC6") (pin "10") (pinfunction "OUTB5_10") (pintype "bidirectional"))
      (node (ref "LED90") (pin "2") (pinfunction "BLUE_2") (pintype "bidirectional"))
    )
    (net (code "119") (name "/N$LEDB91") (class "Default")
      (node (ref "IC6") (pin "44") (pinfunction "OUTB13_44") (pintype "bidirectional"))
      (node (ref "LED91") (pin "2") (pinfunction "BLUE_2") (pintype "bidirectional"))
    )
    (net (code "120") (name "/N$LEDB92") (class "Default")
      (node (ref "IC6") (pin "47") (pinfunction "OUTB9_47") (pintype "bidirectional"))
      (node (ref "LED92") (pin "2") (pinfunction "BLUE_2") (pintype "bidirectional"))
    )
    (net (code "121") (name "/N$LEDB93") (class "Default")
      (node (ref "IC6") (pin "4") (pinfunction "OUTB4_4") (pintype "bidirectional"))
      (node (ref "LED93") (pin "2") (pinfunction "BLUE_2") (pintype "bidirectional"))
    )
    (net (code "122") (name "/N$LEDB94") (class "Default")
      (node (ref "IC6") (pin "7") (pinfunction "OUTB0_7") (pintype "bidirectional"))
      (node (ref "LED94") (pin "2") (pinfunction "BLUE_2") (pintype "bidirectional"))
    )
    (net (code "123") (name "/N$LEDB95") (class "Default")
      (node (ref "IC6") (pin "50") (pinfunction "OUTB12_50") (pintype "bidirectional"))
      (node (ref "LED95") (pin "2") (pinfunction "BLUE_2") (pintype "bidirectional"))
    )
    (net (code "124") (name "/N$LEDB96") (class "Default")
      (node (ref "IC6") (pin "53") (pinfunction "OUTB8_53") (pintype "bidirectional"))
      (node (ref "LED96") (pin "2") (pinfunction "BLUE_2") (pintype "bidirectional"))
    )
    (net (code "125") (name "/N$LEDB97") (class "Default")
      (node (ref "IC7") (pin "25") (pinfunction "OUTB7_25") (pintype "bidirectional"))
      (node (ref "LED97") (pin "2") (pinfunction "BLUE_2") (pintype "bidirectional"))
    )
    (net (code "126") (name "/N$LEDB98") (class "Default")
      (node (ref "IC7") (pin "22") (pinfunction "OUTB3_22") (pintype "bidirectional"))
      (node (ref "LED98") (pin "2") (pinfunction "BLUE_2") (pintype "bidirectional"))
    )
    (net (code "127") (name "/N$LEDB99") (class "Default")
      (node (ref "IC7") (pin "32") (pinfunction "OUTB11_32") (pintype "bidirectional"))
      (node (ref "LED99") (pin "2") (pinfunction "BLUE_2") (pintype "bidirectional"))
    )
    (net (code "128") (name "/N$LEDB100") (class "Default")
      (node (ref "IC7") (pin "35") (pinfunction "OUTB15_35") (pintype "bidirectional"))
      (node (ref "LED100") (pin "2") (pinfunction "BLUE_2") (pintype "bidirectional"))
    )
    (net (code "129") (name "/N$LEDB101") (class "Default")
      (node (ref "IC7") (pin "19") (pinfunction "OUTB6_19") (pintype "bidirectional"))
      (node (ref "LED101") (pin "2") (pinfunction "BLUE_2") (pintype "bidirectional"))
    )
    (net (code "130") (name "/N$LEDB102") (class "Default")
      (node (ref "IC7") (pin "16") (pinfunction "OUTB2_16") (pintype "bidirectional"))
      (node (ref "LED102") (pin "2") (pinfunction "BLUE_2") (pintype "bidirectional"))
    )
    (net (code "131") (name "/N$LEDB103") (class "Default")
      (node (ref "IC7") (pin "38") (pinfunction "OUTB10_38") (pintype "bidirectional"))
      (node (ref "LED103") (pin "2") (pinfunction "BLUE_2") (pintype "bidirectional"))
    )
    (net (code "132") (name "/N$LEDB104") (class "Default")
      (node (ref "IC7") (pin "41") (pinfunction "OUTB14_41") (pintype "bidirectional"))
      (node (ref "LED104") (pin "2") (pinfunction "BLUE_2") (pintype "bidirectional"))
    )
    (net (code "133") (name "/N$LEDB105") (class "Default")
      (node (ref "IC7") (pin "13") (pinfunction "OUTB1_13") (pintype "bidirectional"))
      (node (ref "LED105") (pin "2") (pinfunction "BLUE_2") (pintype "bidirectional"))
    )
    (net (code "134") (name "/N$LEDB106") (class "Default")
      (node (ref "IC7") (pin "10") (pinfunction "OUTB5_10") (pintype "bidirectional"))
      (node (ref "LED106") (pin "2") (pinfunction "BLUE_2") (pintype "bidirectional"))
    )
    (net (code "135") (name "/N$LEDB107") (class "Default")
      (node (ref "IC7") (pin "44") (pinfunction "OUTB13_44") (pintype "bidirectional"))
      (node (ref "LED107") (pin "2") (pinfunction "BLUE_2") (pintype "bidirectional"))
    )
    (net (code "136") (name "/N$LEDB108") (class "Default")
      (node (ref "IC7") (pin "47") (pinfunction "OUTB9_47") (pintype "bidirectional"))
      (node (ref "LED108") (pin "2") (pinfunction "BLUE_2") (pintype "bidirectional"))
    )
    (net (code "137") (name "/N$LEDB109") (class "Default")
      (node (ref "IC7") (pin "4") (pinfunction "OUTB4_4") (pintype "bidirectional"))
      (node (ref "LED109") (pin "2") (pinfunction "BLUE_2") (pintype "bidirectional"))
    )
    (net (code "138") (name "/N$LEDB110") (class "Default")
      (node (ref "IC7") (pin "7") (pinfunction "OUTB0_7") (pintype "bidirectional"))
      (node (ref "LED110") (pin "2") (pinfunction "BLUE_2") (pintype "bidirectional"))
    )
    (net (code "139") (name "/N$LEDB111") (class "Default")
      (node (ref "IC7") (pin "50") (pinfunction "OUTB12_50") (pintype "bidirectional"))
      (node (ref "LED111") (pin "2") (pinfunction "BLUE_2") (pintype "bidirectional"))
    )
    (net (code "140") (name "/N$LEDB112") (class "Default")
      (node (ref "IC7") (pin "53") (pinfunction "OUTB8_53") (pintype "bidirectional"))
      (node (ref "LED112") (pin "2") (pinfunction "BLUE_2") (pintype "bidirectional"))
    )
    (net (code "141") (name "/N$LEDB113") (class "Default")
      (node (ref "IC8") (pin "25") (pinfunction "OUTB7_25") (pintype "bidirectional"))
      (node (ref "LED113") (pin "2") (pinfunction "BLUE_2") (pintype "bidirectional"))
    )
    (net (code "142") (name "/N$LEDB114") (class "Default")
      (node (ref "IC8") (pin "22") (pinfunction "OUTB3_22") (pintype "bidirectional"))
      (node (ref "LED114") (pin "2") (pinfunction "BLUE_2") (pintype "bidirectional"))
    )
    (net (code "143") (name "/N$LEDB115") (class "Default")
      (node (ref "IC8") (pin "32") (pinfunction "OUTB11_32") (pintype "bidirectional"))
      (node (ref "LED115") (pin "2") (pinfunction "BLUE_2") (pintype "bidirectional"))
    )
    (net (code "144") (name "/N$LEDB116") (class "Default")
      (node (ref "IC8") (pin "35") (pinfunction "OUTB15_35") (pintype "bidirectional"))
      (node (ref "LED116") (pin "2") (pinfunction "BLUE_2") (pintype "bidirectional"))
    )
    (net (code "145") (name "/N$LEDB117") (class "Default")
      (node (ref "IC8") (pin "19") (pinfunction "OUTB6_19") (pintype "bidirectional"))
      (node (ref "LED117") (pin "2") (pinfunction "BLUE_2") (pintype "bidirectional"))
    )
    (net (code "146") (name "/N$LEDB118") (class "Default")
      (node (ref "IC8") (pin "16") (pinfunction "OUTB2_16") (pintype "bidirectional"))
      (node (ref "LED118") (pin "2") (pinfunction "BLUE_2") (pintype "bidirectional"))
    )
    (net (code "147") (name "/N$LEDB119") (class "Default")
      (node (ref "IC8") (pin "38") (pinfunction "OUTB10_38") (pintype "bidirectional"))
      (node (ref "LED119") (pin "2") (pinfunction "BLUE_2") (pintype "bidirectional"))
    )
    (net (code "148") (name "/N$LEDB120") (class "Default")
      (node (ref "IC8") (pin "41") (pinfunction "OUTB14_41") (pintype "bidirectional"))
      (node (ref "LED120") (pin "2") (pinfunction "BLUE_2") (pintype "bidirectional"))
    )
    (net (code "149") (name "/N$LEDG1") (class "Default")
      (node (ref "IC1") (pin "27") (pinfunction "OUTG7_27") (pintype "bidirectional"))
      (node (ref "LED1") (pin "1") (pinfunction "GREEN_1") (pintype "bidirectional"))
    )
    (net (code "150") (name "/N$LEDG2") (class "Default")
      (node (ref "IC1") (pin "24") (pinfunction "OUTG3_24") (pintype "bidirectional"))
      (node (ref "LED2") (pin "1") (pinfunction "GREEN_1") (pintype "bidirectional"))
    )
    (net (code "151") (name "/N$LEDG3") (class "Default")
      (node (ref "IC1") (pin "30") (pinfunction "OUTG11_30") (pintype "bidirectional"))
      (node (ref "LED3") (pin "1") (pinfunction "GREEN_1") (pintype "bidirectional"))
    )
    (net (code "152") (name "/N$LEDG4") (class "Default")
      (node (ref "IC1") (pin "33") (pinfunction "OUTG15_33") (pintype "bidirectional"))
      (node (ref "LED4") (pin "1") (pinfunction "GREEN_1") (pintype "bidirectional"))
    )
    (net (code "153") (name "/N$LEDG5") (class "Default")
      (node (ref "IC1") (pin "21") (pinfunction "OUTG6_21") (pintype "bidirectional"))
      (node (ref "LED5") (pin "1") (pinfunction "GREEN_1") (pintype "bidirectional"))
    )
    (net (code "154") (name "/N$LEDG6") (class "Default")
      (node (ref "IC1") (pin "18") (pinfunction "OUTG2_18") (pintype "bidirectional"))
      (node (ref "LED6") (pin "1") (pinfunction "GREEN_1") (pintype "bidirectional"))
    )
    (net (code "155") (name "/N$LEDG7") (class "Default")
      (node (ref "IC1") (pin "36") (pinfunction "OUTG10_36") (pintype "bidirectional"))
      (node (ref "LED7") (pin "1") (pinfunction "GREEN_1") (pintype "bidirectional"))
    )
    (net (code "156") (name "/N$LEDG8") (class "Default")
      (node (ref "IC1") (pin "39") (pinfunction "OUTG14_39") (pintype "bidirectional"))
      (node (ref "LED8") (pin "1") (pinfunction "GREEN_1") (pintype "bidirectional"))
    )
    (net (code "157") (name "/N$LEDG9") (class "Default")
      (node (ref "IC1") (pin "15") (pinfunction "OUTG1_15") (pintype "bidirectional"))
      (node (ref "LED9") (pin "1") (pinfunction "GREEN_1") (pintype "bidirectional"))
    )
    (net (code "158") (name "/N$LEDG10") (class "Default")
      (node (ref "IC1") (pin "12") (pinfunction "OUTG5_12") (pintype "bidirectional"))
      (node (ref "LED10") (pin "1") (pinfunction "GREEN_1") (pintype "bidirectional"))
    )
    (net (code "159") (name "/N$LEDG11") (class "Default")
      (node (ref "IC1") (pin "42") (pinfunction "OUTG13_42") (pintype "bidirectional"))
      (node (ref "LED11") (pin "1") (pinfunction "GREEN_1") (pintype "bidirectional"))
    )
    (net (code "160") (name "/N$LEDG12") (class "Default")
      (node (ref "IC1") (pin "45") (pinfunction "OUTG9_45") (pintype "bidirectional"))
      (node (ref "LED12") (pin "1") (pinfunction "GREEN_1") (pintype "bidirectional"))
    )
    (net (code "161") (name "/N$LEDG13") (class "Default")
      (node (ref "IC1") (pin "6") (pinfunction "OUTG4_6") (pintype "bidirectional"))
      (node (ref "LED13") (pin "1") (pinfunction "GREEN_1") (pintype "bidirectional"))
    )
    (net (code "162") (name "/N$LEDG14") (class "Default")
      (node (ref "IC1") (pin "9") (pinfunction "OUTG0_9") (pintype "bidirectional"))
      (node (ref "LED14") (pin "1") (pinfunction "GREEN_1") (pintype "bidirectional"))
    )
    (net (code "163") (name "/N$LEDG15") (class "Default")
      (node (ref "IC1") (pin "48") (pinfunction "OUTG12_48") (pintype "bidirectional"))
      (node (ref "LED15") (pin "1") (pinfunction "GREEN_1") (pintype "bidirectional"))
    )
    (net (code "164") (name "/N$LEDG16") (class "Default")
      (node (ref "IC1") (pin "51") (pinfunction "OUTG8_51") (pintype "bidirectional"))
      (node (ref "LED16") (pin "1") (pinfunction "GREEN_1") (pintype "bidirectional"))
    )
    (net (code "165") (name "/N$LEDG17") (class "Default")
      (node (ref "IC2") (pin "27") (pinfunction "OUTG7_27") (pintype "bidirectional"))
      (node (ref "LED17") (pin "1") (pinfunction "GREEN_1") (pintype "bidirectional"))
    )
    (net (code "166") (name "/N$LEDG18") (class "Default")
      (node (ref "IC2") (pin "24") (pinfunction "OUTG3_24") (pintype "bidirectional"))
      (node (ref "LED18") (pin "1") (pinfunction "GREEN_1") (pintype "bidirectional"))
    )
    (net (code "167") (name "/N$LEDG19") (class "Default")
      (node (ref "IC2") (pin "30") (pinfunction "OUTG11_30") (pintype "bidirectional"))
      (node (ref "LED19") (pin "1") (pinfunction "GREEN_1") (pintype "bidirectional"))
    )
    (net (code "168") (name "/N$LEDG20") (class "Default")
      (node (ref "IC2") (pin "33") (pinfunction "OUTG15_33") (pintype "bidirectional"))
      (node (ref "LED20") (pin "1") (pinfunction "GREEN_1") (pintype "bidirectional"))
    )
    (net (code "169") (name "/N$LEDG21") (class "Default")
      (node (ref "IC2") (pin "21") (pinfunction "OUTG6_21") (pintype "bidirectional"))
      (node (ref "LED21") (pin "1") (pinfunction "GREEN_1") (pintype "bidirectional"))
    )
    (net (code "170") (name "/N$LEDG22") (class "Default")
      (node (ref "IC2") (pin "18") (pinfunction "OUTG2_18") (pintype "bidirectional"))
      (node (ref "LED22") (pin "1") (pinfunction "GREEN_1") (pintype "bidirectional"))
    )
    (net (code "171") (name "/N$LEDG23") (class "Default")
      (node (ref "IC2") (pin "36") (pinfunction "OUTG10_36") (pintype "bidirectional"))
      (node (ref "LED23") (pin "1") (pinfunction "GREEN_1") (pintype "bidirectional"))
    )
    (net (code "172") (name "/N$LEDG24") (class "Default")
      (node (ref "IC2") (pin "39") (pinfunction "OUTG14_39") (pintype "bidirectional"))
      (node (ref "LED24") (pin "1") (pinfunction "GREEN_1") (pintype "bidirectional"))
    )
    (net (code "173") (name "/N$LEDG25") (class "Default")
      (node (ref "IC2") (pin "15") (pinfunction "OUTG1_15") (pintype "bidirectional"))
      (node (ref "LED25") (pin "1") (pinfunction "GREEN_1") (pintype "bidirectional"))
    )
    (net (code "174") (name "/N$LEDG26") (class "Default")
      (node (ref "IC2") (pin "12") (pinfunction "OUTG5_12") (pintype "bidirectional"))
      (node (ref "LED26") (pin "1") (pinfunction "GREEN_1") (pintype "bidirectional"))
    )
    (net (code "175") (name "/N$LEDG27") (class "Default")
      (node (ref "IC2") (pin "42") (pinfunction "OUTG13_42") (pintype "bidirectional"))
      (node (ref "LED27") (pin "1") (pinfunction "GREEN_1") (pintype "bidirectional"))
    )
    (net (code "176") (name "/N$LEDG28") (class "Default")
      (node (ref "IC2") (pin "45") (pinfunction "OUTG9_45") (pintype "bidirectional"))
      (node (ref "LED28") (pin "1") (pinfunction "GREEN_1") (pintype "bidirectional"))
    )
    (net (code "177") (name "/N$LEDG29") (class "Default")
      (node (ref "IC2") (pin "6") (pinfunction "OUTG4_6") (pintype "bidirectional"))
      (node (ref "LED29") (pin "1") (pinfunction "GREEN_1") (pintype "bidirectional"))
    )
    (net (code "178") (name "/N$LEDG30") (class "Default")
      (node (ref "IC2") (pin "9") (pinfunction "OUTG0_9") (pintype "bidirectional"))
      (node (ref "LED30") (pin "1") (pinfunction "GREEN_1") (pintype "bidirectional"))
    )
    (net (code "179") (name "/N$LEDG31") (class "Default")
      (node (ref "IC2") (pin "48") (pinfunction "OUTG12_48") (pintype "bidirectional"))
      (node (ref "LED31") (pin "1") (pinfunction "GREEN_1") (pintype "bidirectional"))
    )
    (net (code "180") (name "/N$LEDG32") (class "Default")
      (node (ref "IC2") (pin "51") (pinfunction "OUTG8_51") (pintype "bidirectional"))
      (node (ref "LED32") (pin "1") (pinfunction "GREEN_1") (pintype "bidirectional"))
    )
    (net (code "181") (name "/N$LEDG33") (class "Default")
      (node (ref "IC3") (pin "27") (pinfunction "OUTG7_27") (pintype "bidirectional"))
      (node (ref "LED33") (pin "1") (pinfunction "GREEN_1") (pintype "bidirectional"))
    )
    (net (code "182") (name "/N$LEDG34") (class "Default")
      (node (ref "IC3") (pin "24") (pinfunction "OUTG3_24") (pintype "bidirectional"))
      (node (ref "LED34") (pin "1") (pinfunction "GREEN_1") (pintype "bidirectional"))
    )
    (net (code "183") (name "/N$LEDG35") (class "Default")
      (node (ref "IC3") (pin "30") (pinfunction "OUTG11_30") (pintype "bidirectional"))
      (node (ref "LED35") (pin "1") (pinfunction "GREEN_1") (pintype "bidirectional"))
    )
    (net (code "184") (name "/N$LEDG36") (class "Default")
      (node (ref "IC3") (pin "33") (pinfunction "OUTG15_33") (pintype "bidirectional"))
      (node (ref "LED36") (pin "1") (pinfunction "GREEN_1") (pintype "bidirectional"))
    )
    (net (code "185") (name "/N$LEDG37") (class "Default")
      (node (ref "IC3") (pin "21") (pinfunction "OUTG6_21") (pintype "bidirectional"))
      (node (ref "LED37") (pin "1") (pinfunction "GREEN_1") (pintype "bidirectional"))
    )
    (net (code "186") (name "/N$LEDG38") (class "Default")
      (node (ref "IC3") (pin "18") (pinfunction "OUTG2_18") (pintype "bidirectional"))
      (node (ref "LED38") (pin "1") (pinfunction "GREEN_1") (pintype "bidirectional"))
    )
    (net (code "187") (name "/N$LEDG39") (class "Default")
      (node (ref "IC3") (pin "36") (pinfunction "OUTG10_36") (pintype "bidirectional"))
      (node (ref "LED39") (pin "1") (pinfunction "GREEN_1") (pintype "bidirectional"))
    )
    (net (code "188") (name "/N$LEDG40") (class "Default")
      (node (ref "IC3") (pin "39") (pinfunction "OUTG14_39") (pintype "bidirectional"))
      (node (ref "LED40") (pin "1") (pinfunction "GREEN_1") (pintype "bidirectional"))
    )
    (net (code "189") (name "/N$LEDG41") (class "Default")
      (node (ref "IC3") (pin "15") (pinfunction "OUTG1_15") (pintype "bidirectional"))
      (node (ref "LED41") (pin "1") (pinfunction "GREEN_1") (pintype "bidirectional"))
    )
    (net (code "190") (name "/N$LEDG42") (class "Default")
      (node (ref "IC3") (pin "12") (pinfunction "OUTG5_12") (pintype "bidirectional"))
      (node (ref "LED42") (pin "1") (pinfunction "GREEN_1") (pintype "bidirectional"))
    )
    (net (code "191") (name "/N$LEDG43") (class "Default")
      (node (ref "IC3") (pin "42") (pinfunction "OUTG13_42") (pintype "bidirectional"))
      (node (ref "LED43") (pin "1") (pinfunction "GREEN_1") (pintype "bidirectional"))
    )
    (net (code "192") (name "/N$LEDG44") (class "Default")
      (node (ref "IC3") (pin "45") (pinfunction "OUTG9_45") (pintype "bidirectional"))
      (node (ref "LED44") (pin "1") (pinfunction "GREEN_1") (pintype "bidirectional"))
    )
    (net (code "193") (name "/N$LEDG45") (class "Default")
      (node (ref "IC3") (pin "6") (pinfunction "OUTG4_6") (pintype "bidirectional"))
      (node (ref "LED45") (pin "1") (pinfunction "GREEN_1") (pintype "bidirectional"))
    )
    (net (code "194") (name "/N$LEDG46") (class "Default")
      (node (ref "IC3") (pin "9") (pinfunction "OUTG0_9") (pintype "bidirectional"))
      (node (ref "LED46") (pin "1") (pinfunction "GREEN_1") (pintype "bidirectional"))
    )
    (net (code "195") (name "/N$LEDG47") (class "Default")
      (node (ref "IC3") (pin "48") (pinfunction "OUTG12_48") (pintype "bidirectional"))
      (node (ref "LED47") (pin "1") (pinfunction "GREEN_1") (pintype "bidirectional"))
    )
    (net (code "196") (name "/N$LEDG48") (class "Default")
      (node (ref "IC3") (pin "51") (pinfunction "OUTG8_51") (pintype "bidirectional"))
      (node (ref "LED48") (pin "1") (pinfunction "GREEN_1") (pintype "bidirectional"))
    )
    (net (code "197") (name "/N$LEDG49") (class "Default")
      (node (ref "IC4") (pin "27") (pinfunction "OUTG7_27") (pintype "bidirectional"))
      (node (ref "LED49") (pin "1") (pinfunction "GREEN_1") (pintype "bidirectional"))
    )
    (net (code "198") (name "/N$LEDG50") (class "Default")
      (node (ref "IC4") (pin "24") (pinfunction "OUTG3_24") (pintype "bidirectional"))
      (node (ref "LED50") (pin "1") (pinfunction "GREEN_1") (pintype "bidirectional"))
    )
    (net (code "199") (name "/N$LEDG51") (class "Default")
      (node (ref "IC4") (pin "30") (pinfunction "OUTG11_30") (pintype "bidirectional"))
      (node (ref "LED51") (pin "1") (pinfunction "GREEN_1") (pintype "bidirectional"))
    )
    (net (code "200") (name "/N$LEDG52") (class "Default")
      (node (ref "IC4") (pin "33") (pinfunction "OUTG15_33") (pintype "bidirectional"))
      (node (ref "LED52") (pin "1") (pinfunction "GREEN_1") (pintype "bidirectional"))
    )
    (net (code "201") (name "/N$LEDG53") (class "Default")
      (node (ref "IC4") (pin "21") (pinfunction "OUTG6_21") (pintype "bidirectional"))
      (node (ref "LED53") (pin "1") (pinfunction "GREEN_1") (pintype "bidirectional"))
    )
    (net (code "202") (name "/N$LEDG54") (class "Default")
      (node (ref "IC4") (pin "18") (pinfunction "OUTG2_18") (pintype "bidirectional"))
      (node (ref "LED54") (pin "1") (pinfunction "GREEN_1") (pintype "bidirectional"))
    )
    (net (code "203") (name "/N$LEDG55") (class "Default")
      (node (ref "IC4") (pin "36") (pinfunction "OUTG10_36") (pintype "bidirectional"))
      (node (ref "LED55") (pin "1") (pinfunction "GREEN_1") (pintype "bidirectional"))
    )
    (net (code "204") (name "/N$LEDG56") (class "Default")
      (node (ref "IC4") (pin "39") (pinfunction "OUTG14_39") (pintype "bidirectional"))
      (node (ref "LED56") (pin "1") (pinfunction "GREEN_1") (pintype "bidirectional"))
    )
    (net (code "205") (name "/N$LEDG57") (class "Default")
      (node (ref "IC4") (pin "15") (pinfunction "OUTG1_15") (pintype "bidirectional"))
      (node (ref "LED57") (pin "1") (pinfunction "GREEN_1") (pintype "bidirectional"))
    )
    (net (code "206") (name "/N$LEDG58") (class "Default")
      (node (ref "IC4") (pin "12") (pinfunction "OUTG5_12") (pintype "bidirectional"))
      (node (ref "LED58") (pin "1") (pinfunction "GREEN_1") (pintype "bidirectional"))
    )
    (net (code "207") (name "/N$LEDG59") (class "Default")
      (node (ref "IC4") (pin "42") (pinfunction "OUTG13_42") (pintype "bidirectional"))
      (node (ref "LED59") (pin "1") (pinfunction "GREEN_1") (pintype "bidirectional"))
    )
    (net (code "208") (name "/N$LEDG60") (class "Default")
      (node (ref "IC4") (pin "45") (pinfunction "OUTG9_45") (pintype "bidirectional"))
      (node (ref "LED60") (pin "1") (pinfunction "GREEN_1") (pintype "bidirectional"))
    )
    (net (code "209") (name "/N$LEDG61") (class "Default")
      (node (ref "IC4") (pin "6") (pinfunction "OUTG4_6") (pintype "bidirectional"))
      (node (ref "LED61") (pin "1") (pinfunction "GREEN_1") (pintype "bidirectional"))
    )
    (net (code "210") (name "/N$LEDG62") (class "Default")
      (node (ref "IC4") (pin "9") (pinfunction "OUTG0_9") (pintype "bidirectional"))
      (node (ref "LED62") (pin "1") (pinfunction "GREEN_1") (pintype "bidirectional"))
    )
    (net (code "211") (name "/N$LEDG63") (class "Default")
      (node (ref "IC4") (pin "48") (pinfunction "OUTG12_48") (pintype "bidirectional"))
      (node (ref "LED63") (pin "1") (pinfunction "GREEN_1") (pintype "bidirectional"))
    )
    (net (code "212") (name "/N$LEDG64") (class "Default")
      (node (ref "IC4") (pin "51") (pinfunction "OUTG8_51") (pintype "bidirectional"))
      (node (ref "LED64") (pin "1") (pinfunction "GREEN_1") (pintype "bidirectional"))
    )
    (net (code "213") (name "/N$LEDG65") (class "Default")
      (node (ref "IC5") (pin "27") (pinfunction "OUTG7_27") (pintype "bidirectional"))
      (node (ref "LED65") (pin "1") (pinfunction "GREEN_1") (pintype "bidirectional"))
    )
    (net (code "214") (name "/N$LEDG66") (class "Default")
      (node (ref "IC5") (pin "24") (pinfunction "OUTG3_24") (pintype "bidirectional"))
      (node (ref "LED66") (pin "1") (pinfunction "GREEN_1") (pintype "bidirectional"))
    )
    (net (code "215") (name "/N$LEDG67") (class "Default")
      (node (ref "IC5") (pin "30") (pinfunction "OUTG11_30") (pintype "bidirectional"))
      (node (ref "LED67") (pin "1") (pinfunction "GREEN_1") (pintype "bidirectional"))
    )
    (net (code "216") (name "/N$LEDG68") (class "Default")
      (node (ref "IC5") (pin "33") (pinfunction "OUTG15_33") (pintype "bidirectional"))
      (node (ref "LED68") (pin "1") (pinfunction "GREEN_1") (pintype "bidirectional"))
    )
    (net (code "217") (name "/N$LEDG69") (class "Default")
      (node (ref "IC5") (pin "21") (pinfunction "OUTG6_21") (pintype "bidirectional"))
      (node (ref "LED69") (pin "1") (pinfunction "GREEN_1") (pintype "bidirectional"))
    )
    (net (code "218") (name "/N$LEDG70") (class "Default")
      (node (ref "IC5") (pin "18") (pinfunction "OUTG2_18") (pintype "bidirectional"))
      (node (ref "LED70") (pin "1") (pinfunction "GREEN_1") (pintype "bidirectional"))
    )
    (net (code "219") (name "/N$LEDG71") (class "Default")
      (node (ref "IC5") (pin "36") (pinfunction "OUTG10_36") (pintype "bidirectional"))
      (node (ref "LED71") (pin "1") (pinfunction "GREEN_1") (pintype "bidirectional"))
    )
    (net (code "220") (name "/N$LEDG72") (class "Default")
      (node (ref "IC5") (pin "39") (pinfunction "OUTG14_39") (pintype "bidirectional"))
      (node (ref "LED72") (pin "1") (pinfunction "GREEN_1") (pintype "bidirectional"))
    )
    (net (code "221") (name "/N$LEDG73") (class "Default")
      (node (ref "IC5") (pin "15") (pinfunction "OUTG1_15") (pintype "bidirectional"))
      (node (ref "LED73") (pin "1") (pinfunction "GREEN_1") (pintype "bidirectional"))
    )
    (net (code "222") (name "/N$LEDG74") (class "Default")
      (node (ref "IC5") (pin "12") (pinfunction "OUTG5_12") (pintype "bidirectional"))
      (node (ref "LED74") (pin "1") (pinfunction "GREEN_1") (pintype "bidirectional"))
    )
    (net (code "223") (name "/N$LEDG75") (class "Default")
      (node (ref "IC5") (pin "42") (pinfunction "OUTG13_42") (pintype "bidirectional"))
      (node (ref "LED75") (pin "1") (pinfunction "GREEN_1") (pintype "bidirectional"))
    )
    (net (code "224") (name "/N$LEDG76") (class "Default")
      (node (ref "IC5") (pin "45") (pinfunction "OUTG9_45") (pintype "bidirectional"))
      (node (ref "LED76") (pin "1") (pinfunction "GREEN_1") (pintype "bidirectional"))
    )
    (net (code "225") (name "/N$LEDG77") (class "Default")
      (node (ref "IC5") (pin "6") (pinfunction "OUTG4_6") (pintype "bidirectional"))
      (node (ref "LED77") (pin "1") (pinfunction "GREEN_1") (pintype "bidirectional"))
    )
    (net (code "226") (name "/N$LEDG78") (class "Default")
      (node (ref "IC5") (pin "9") (pinfunction "OUTG0_9") (pintype "bidirectional"))
      (node (ref "LED78") (pin "1") (pinfunction "GREEN_1") (pintype "bidirectional"))
    )
    (net (code "227") (name "/N$LEDG79") (class "Default")
      (node (ref "IC5") (pin "48") (pinfunction "OUTG12_48") (pintype "bidirectional"))
      (node (ref "LED79") (pin "1") (pinfunction "GREEN_1") (pintype "bidirectional"))
    )
    (net (code "228") (name "/N$LEDG80") (class "Default")
      (node (ref "IC5") (pin "51") (pinfunction "OUTG8_51") (pintype "bidirectional"))
      (node (ref "LED80") (pin "1") (pinfunction "GREEN_1") (pintype "bidirectional"))
    )
    (net (code "229") (name "/N$LEDG81") (class "Default")
      (node (ref "IC6") (pin "27") (pinfunction "OUTG7_27") (pintype "bidirectional"))
      (node (ref "LED81") (pin "1") (pinfunction "GREEN_1") (pintype "bidirectional"))
    )
    (net (code "230") (name "/N$LEDG82") (class "Default")
      (node (ref "IC6") (pin "24") (pinfunction "OUTG3_24") (pintype "bidirectional"))
      (node (ref "LED82") (pin "1") (pinfunction "GREEN_1") (pintype "bidirectional"))
    )
    (net (code "231") (name "/N$LEDG83") (class "Default")
      (node (ref "IC6") (pin "30") (pinfunction "OUTG11_30") (pintype "bidirectional"))
      (node (ref "LED83") (pin "1") (pinfunction "GREEN_1") (pintype "bidirectional"))
    )
    (net (code "232") (name "/N$LEDG84") (class "Default")
      (node (ref "IC6") (pin "33") (pinfunction "OUTG15_33") (pintype "bidirectional"))
      (node (ref "LED84") (pin "1") (pinfunction "GREEN_1") (pintype "bidirectional"))
    )
    (net (code "233") (name "/N$LEDG85") (class "Default")
      (node (ref "IC6") (pin "21") (pinfunction "OUTG6_21") (pintype "bidirectional"))
      (node (ref "LED85") (pin "1") (pinfunction "GREEN_1") (pintype "bidirectional"))
    )
    (net (code "234") (name "/N$LEDG86") (class "Default")
      (node (ref "IC6") (pin "18") (pinfunction "OUTG2_18") (pintype "bidirectional"))
      (node (ref "LED86") (pin "1") (pinfunction "GREEN_1") (pintype "bidirectional"))
    )
    (net (code "235") (name "/N$LEDG87") (class "Default")
      (node (ref "IC6") (pin "36") (pinfunction "OUTG10_36") (pintype "bidirectional"))
      (node (ref "LED87") (pin "1") (pinfunction "GREEN_1") (pintype "bidirectional"))
    )
    (net (code "236") (name "/N$LEDG88") (class "Default")
      (node (ref "IC6") (pin "39") (pinfunction "OUTG14_39") (pintype "bidirectional"))
      (node (ref "LED88") (pin "1") (pinfunction "GREEN_1") (pintype "bidirectional"))
    )
    (net (code "237") (name "/N$LEDG89") (class "Default")
      (node (ref "IC6") (pin "15") (pinfunction "OUTG1_15") (pintype "bidirectional"))
      (node (ref "LED89") (pin "1") (pinfunction "GREEN_1") (pintype "bidirectional"))
    )
    (net (code "238") (name "/N$LEDG90") (class "Default")
      (node (ref "IC6") (pin "12") (pinfunction "OUTG5_12") (pintype "bidirectional"))
      (node (ref "LED90") (pin "1") (pinfunction "GREEN_1") (pintype "bidirectional"))
    )
    (net (code "239") (name "/N$LEDG91") (class "Default")
      (node (ref "IC6") (pin "42") (pinfunction "OUTG13_42") (pintype "bidirectional"))
      (node (ref "LED91") (pin "1") (pinfunction "GREEN_1") (pintype "bidirectional"))
    )
    (net (code "240") (name "/N$LEDG92") (class "Default")
      (node (ref "IC6") (pin "45") (pinfunction "OUTG9_45") (pintype "bidirectional"))
      (node (ref "LED92") (pin "1") (pinfunction "GREEN_1") (pintype "bidirectional"))
    )
    (net (code "241") (name "/N$LEDG93") (class "Default")
      (node (ref "IC6") (pin "6") (pinfunction "OUTG4_6") (pintype "bidirectional"))
      (node (ref "LED93") (pin "1") (pinfunction "GREEN_1") (pintype "bidirectional"))
    )
    (net (code "242") (name "/N$LEDG94") (class "Default")
      (node (ref "IC6") (pin "9") (pinfunction "OUTG0_9") (pintype "bidirectional"))
      (node (ref "LED94") (pin "1") (pinfunction "GREEN_1") (pintype "bidirectional"))
    )
    (net (code "243") (name "/N$LEDG95") (class "Default")
      (node (ref "IC6") (pin "48") (pinfunction "OUTG12_48") (pintype "bidirectional"))
      (node (ref "LED95") (pin "1") (pinfunction "GREEN_1") (pintype "bidirectional"))
    )
    (net (code "244") (name "/N$LEDG96") (class "Default")
      (node (ref "IC6") (pin "51") (pinfunction "OUTG8_51") (pintype "bidirectional"))
      (node (ref "LED96") (pin "1") (pinfunction "GREEN_1") (pintype "bidirectional"))
    )
    (net (code "245") (name "/N$LEDG97") (class "Default")
      (node (ref "IC7") (pin "27") (pinfunction "OUTG7_27") (pintype "bidirectional"))
      (node (ref "LED97") (pin "1") (pinfunction "GREEN_1") (pintype "bidirectional"))
    )
    (net (code "246") (name "/N$LEDG98") (class "Default")
      (node (ref "IC7") (pin "24") (pinfunction "OUTG3_24") (pintype "bidirectional"))
      (node (ref "LED98") (pin "1") (pinfunction "GREEN_1") (pintype "bidirectional"))
    )
    (net (code "247") (name "/N$LEDG99") (class "Default")
      (node (ref "IC7") (pin "30") (pinfunction "OUTG11_30") (pintype "bidirectional"))
      (node (ref "LED99") (pin "1") (pinfunction "GREEN_1") (pintype "bidirectional"))
    )
    (net (code "248") (name "/N$LEDG100") (class "Default")
      (node (ref "IC7") (pin "33") (pinfunction "OUTG15_33") (pintype "bidirectional"))
      (node (ref "LED100") (pin "1") (pinfunction "GREEN_1") (pintype "bidirectional"))
    )
    (net (code "249") (name "/N$LEDG101") (class "Default")
      (node (ref "IC7") (pin "21") (pinfunction "OUTG6_21") (pintype "bidirectional"))
      (node (ref "LED101") (pin "1") (pinfunction "GREEN_1") (pintype "bidirectional"))
    )
    (net (code "250") (name "/N$LEDG102") (class "Default")
      (node (ref "IC7") (pin "18") (pinfunction "OUTG2_18") (pintype "bidirectional"))
      (node (ref "LED102") (pin "1") (pinfunction "GREEN_1") (pintype "bidirectional"))
    )
    (net (code "251") (name "/N$LEDG103") (class "Default")
      (node (ref "IC7") (pin "36") (pinfunction "OUTG10_36") (pintype "bidirectional"))
      (node (ref "LED103") (pin "1") (pinfunction "GREEN_1") (pintype "bidirectional"))
    )
    (net (code "252") (name "/N$LEDG104") (class "Default")
      (node (ref "IC7") (pin "39") (pinfunction "OUTG14_39") (pintype "bidirectional"))
      (node (ref "LED104") (pin "1") (pinfunction "GREEN_1") (pintype "bidirectional"))
    )
    (net (code "253") (name "/N$LEDG105") (class "Default")
      (node (ref "IC7") (pin "15") (pinfunction "OUTG1_15") (pintype "bidirectional"))
      (node (ref "LED105") (pin "1") (pinfunction "GREEN_1") (pintype "bidirectional"))
    )
    (net (code "254") (name "/N$LEDG106") (class "Default")
      (node (ref "IC7") (pin "12") (pinfunction "OUTG5_12") (pintype "bidirectional"))
      (node (ref "LED106") (pin "1") (pinfunction "GREEN_1") (pintype "bidirectional"))
    )
    (net (code "255") (name "/N$LEDG107") (class "Default")
      (node (ref "IC7") (pin "42") (pinfunction "OUTG13_42") (pintype "bidirectional"))
      (node (ref "LED107") (pin "1") (pinfunction "GREEN_1") (pintype "bidirectional"))
    )
    (net (code "256") (name "/N$LEDG108") (class "Default")
      (node (ref "IC7") (pin "45") (pinfunction "OUTG9_45") (pintype "bidirectional"))
      (node (ref "LED108") (pin "1") (pinfunction "GREEN_1") (pintype "bidirectional"))
    )
    (net (code "257") (name "/N$LEDG109") (class "Default")
      (node (ref "IC7") (pin "6") (pinfunction "OUTG4_6") (pintype "bidirectional"))
      (node (ref "LED109") (pin "1") (pinfunction "GREEN_1") (pintype "bidirectional"))
    )
    (net (code "258") (name "/N$LEDG110") (class "Default")
      (node (ref "IC7") (pin "9") (pinfunction "OUTG0_9") (pintype "bidirectional"))
      (node (ref "LED110") (pin "1") (pinfunction "GREEN_1") (pintype "bidirectional"))
    )
    (net (code "259") (name "/N$LEDG111") (class "Default")
      (node (ref "IC7") (pin "48") (pinfunction "OUTG12_48") (pintype "bidirectional"))
      (node (ref "LED111") (pin "1") (pinfunction "GREEN_1") (pintype "bidirectional"))
    )
    (net (code "260") (name "/N$LEDG112") (class "Default")
      (node (ref "IC7") (pin "51") (pinfunction "OUTG8_51") (pintype "bidirectional"))
      (node (ref "LED112") (pin "1") (pinfunction "GREEN_1") (pintype "bidirectional"))
    )
    (net (code "261") (name "/N$LEDG113") (class "Default")
      (node (ref "IC8") (pin "27") (pinfunction "OUTG7_27") (pintype "bidirectional"))
      (node (ref "LED113") (pin "1") (pinfunction "GREEN_1") (pintype "bidirectional"))
    )
    (net (code "262") (name "/N$LEDG114") (class "Default")
      (node (ref "IC8") (pin "24") (pinfunction "OUTG3_24") (pintype "bidirectional"))
      (node (ref "LED114") (pin "1") (pinfunction "GREEN_1") (pintype "bidirectional"))
    )
    (net (code "263") (name "/N$LEDG115") (class "Default")
      (node (ref "IC8") (pin "30") (pinfunction "OUTG11_30") (pintype "bidirectional"))
      (node (ref "LED115") (pin "1") (pinfunction "GREEN_1") (pintype "bidirectional"))
    )
    (net (code "264") (name "/N$LEDG116") (class "Default")
      (node (ref "IC8") (pin "33") (pinfunction "OUTG15_33") (pintype "bidirectional"))
      (node (ref "LED116") (pin "1") (pinfunction "GREEN_1") (pintype "bidirectional"))
    )
    (net (code "265") (name "/N$LEDG117") (class "Default")
      (node (ref "IC8") (pin "21") (pinfunction "OUTG6_21") (pintype "bidirectional"))
      (node (ref "LED117") (pin "1") (pinfunction "GREEN_1") (pintype "bidirectional"))
    )
    (net (code "266") (name "/N$LEDG118") (class "Default")
      (node (ref "IC8") (pin "18") (pinfunction "OUTG2_18") (pintype "bidirectional"))
      (node (ref "LED118") (pin "1") (pinfunction "GREEN_1") (pintype "bidirectional"))
    )
    (net (code "267") (name "/N$LEDG119") (class "Default")
      (node (ref "IC8") (pin "36") (pinfunction "OUTG10_36") (pintype "bidirectional"))
      (node (ref "LED119") (pin "1") (pinfunction "GREEN_1") (pintype "bidirectional"))
    )
    (net (code "268") (name "/N$LEDG120") (class "Default")
      (node (ref "IC8") (pin "39") (pinfunction "OUTG14_39") (pintype "bidirectional"))
      (node (ref "LED120") (pin "1") (pinfunction "GREEN_1") (pintype "bidirectional"))
    )
    (net (code "269") (name "/N$LEDR1") (class "Default")
      (node (ref "IC1") (pin "26") (pinfunction "OUTR7_26") (pintype "bidirectional"))
      (node (ref "LED1") (pin "4") (pinfunction "RED_4") (pintype "bidirectional"))
    )
    (net (code "270") (name "/N$LEDR2") (class "Default")
      (node (ref "IC1") (pin "23") (pinfunction "OUTR3_23") (pintype "bidirectional"))
      (node (ref "LED2") (pin "4") (pinfunction "RED_4") (pintype "bidirectional"))
    )
    (net (code "271") (name "/N$LEDR3") (class "Default")
      (node (ref "IC1") (pin "31") (pinfunction "OUTR11_31") (pintype "bidirectional"))
      (node (ref "LED3") (pin "4") (pinfunction "RED_4") (pintype "bidirectional"))
    )
    (net (code "272") (name "/N$LEDR4") (class "Default")
      (node (ref "IC1") (pin "34") (pinfunction "OUTR15_34") (pintype "bidirectional"))
      (node (ref "LED4") (pin "4") (pinfunction "RED_4") (pintype "bidirectional"))
    )
    (net (code "273") (name "/N$LEDR5") (class "Default")
      (node (ref "IC1") (pin "20") (pinfunction "OUTR6_20") (pintype "bidirectional"))
      (node (ref "LED5") (pin "4") (pinfunction "RED_4") (pintype "bidirectional"))
    )
    (net (code "274") (name "/N$LEDR6") (class "Default")
      (node (ref "IC1") (pin "17") (pinfunction "OUTR2_17") (pintype "bidirectional"))
      (node (ref "LED6") (pin "4") (pinfunction "RED_4") (pintype "bidirectional"))
    )
    (net (code "275") (name "/N$LEDR7") (class "Default")
      (node (ref "IC1") (pin "37") (pinfunction "OUTR10_37") (pintype "bidirectional"))
      (node (ref "LED7") (pin "4") (pinfunction "RED_4") (pintype "bidirectional"))
    )
    (net (code "276") (name "/N$LEDR8") (class "Default")
      (node (ref "IC1") (pin "40") (pinfunction "OUTR14_40") (pintype "bidirectional"))
      (node (ref "LED8") (pin "4") (pinfunction "RED_4") (pintype "bidirectional"))
    )
    (net (code "277") (name "/N$LEDR9") (class "Default")
      (node (ref "IC1") (pin "14") (pinfunction "OUTR1_14") (pintype "bidirectional"))
      (node (ref "LED9") (pin "4") (pinfunction "RED_4") (pintype "bidirectional"))
    )
    (net (code "278") (name "/N$LEDR10") (class "Default")
      (node (ref "IC1") (pin "11") (pinfunction "OUTR5_11") (pintype "bidirectional"))
      (node (ref "LED10") (pin "4") (pinfunction "RED_4") (pintype "bidirectional"))
    )
    (net (code "279") (name "/N$LEDR11") (class "Default")
      (node (ref "IC1") (pin "43") (pinfunction "OUTR13_43") (pintype "bidirectional"))
      (node (ref "LED11") (pin "4") (pinfunction "RED_4") (pintype "bidirectional"))
    )
    (net (code "280") (name "/N$LEDR12") (class "Default")
      (node (ref "IC1") (pin "46") (pinfunction "OUTR9_46") (pintype "bidirectional"))
      (node (ref "LED12") (pin "4") (pinfunction "RED_4") (pintype "bidirectional"))
    )
    (net (code "281") (name "/N$LEDR13") (class "Default")
      (node (ref "IC1") (pin "5") (pinfunction "OUTR4_5") (pintype "bidirectional"))
      (node (ref "LED13") (pin "4") (pinfunction "RED_4") (pintype "bidirectional"))
    )
    (net (code "282") (name "/N$LEDR14") (class "Default")
      (node (ref "IC1") (pin "8") (pinfunction "OUTR0_8") (pintype "bidirectional"))
      (node (ref "LED14") (pin "4") (pinfunction "RED_4") (pintype "bidirectional"))
    )
    (net (code "283") (name "/N$LEDR15") (class "Default")
      (node (ref "IC1") (pin "49") (pinfunction "OUTR12_49") (pintype "bidirectional"))
      (node (ref "LED15") (pin "4") (pinfunction "RED_4") (pintype "bidirectional"))
    )
    (net (code "284") (name "/N$LEDR16") (class "Default")
      (node (ref "IC1") (pin "52") (pinfunction "OUTR8_52") (pintype "bidirectional"))
      (node (ref "LED16") (pin "4") (pinfunction "RED_4") (pintype "bidirectional"))
    )
    (net (code "285") (name "/N$LEDR17") (class "Default")
      (node (ref "IC2") (pin "26") (pinfunction "OUTR7_26") (pintype "bidirectional"))
      (node (ref "LED17") (pin "4") (pinfunction "RED_4") (pintype "bidirectional"))
    )
    (net (code "286") (name "/N$LEDR18") (class "Default")
      (node (ref "IC2") (pin "23") (pinfunction "OUTR3_23") (pintype "bidirectional"))
      (node (ref "LED18") (pin "4") (pinfunction "RED_4") (pintype "bidirectional"))
    )
    (net (code "287") (name "/N$LEDR19") (class "Default")
      (node (ref "IC2") (pin "31") (pinfunction "OUTR11_31") (pintype "bidirectional"))
      (node (ref "LED19") (pin "4") (pinfunction "RED_4") (pintype "bidirectional"))
    )
    (net (code "288") (name "/N$LEDR20") (class "Default")
      (node (ref "IC2") (pin "34") (pinfunction "OUTR15_34") (pintype "bidirectional"))
      (node (ref "LED20") (pin "4") (pinfunction "RED_4") (pintype "bidirectional"))
    )
    (net (code "289") (name "/N$LEDR21") (class "Default")
      (node (ref "IC2") (pin "20") (pinfunction "OUTR6_20") (pintype "bidirectional"))
      (node (ref "LED21") (pin "4") (pinfunction "RED_4") (pintype "bidirectional"))
    )
    (net (code "290") (name "/N$LEDR22") (class "Default")
      (node (ref "IC2") (pin "17") (pinfunction "OUTR2_17") (pintype "bidirectional"))
      (node (ref "LED22") (pin "4") (pinfunction "RED_4") (pintype "bidirectional"))
    )
    (net (code "291") (name "/N$LEDR23") (class "Default")
      (node (ref "IC2") (pin "37") (pinfunction "OUTR10_37") (pintype "bidirectional"))
      (node (ref "LED23") (pin "4") (pinfunction "RED_4") (pintype "bidirectional"))
    )
    (net (code "292") (name "/N$LEDR24") (class "Default")
      (node (ref "IC2") (pin "40") (pinfunction "OUTR14_40") (pintype "bidirectional"))
      (node (ref "LED24") (pin "4") (pinfunction "RED_4") (pintype "bidirectional"))
    )
    (net (code "293") (name "/N$LEDR25") (class "Default")
      (node (ref "IC2") (pin "14") (pinfunction "OUTR1_14") (pintype "bidirectional"))
      (node (ref "LED25") (pin "4") (pinfunction "RED_4") (pintype "bidirectional"))
    )
    (net (code "294") (name "/N$LEDR26") (class "Default")
      (node (ref "IC2") (pin "11") (pinfunction "OUTR5_11") (pintype "bidirectional"))
      (node (ref "LED26") (pin "4") (pinfunction "RED_4") (pintype "bidirectional"))
    )
    (net (code "295") (name "/N$LEDR27") (class "Default")
      (node (ref "IC2") (pin "43") (pinfunction "OUTR13_43") (pintype "bidirectional"))
      (node (ref "LED27") (pin "4") (pinfunction "RED_4") (pintype "bidirectional"))
    )
    (net (code "296") (name "/N$LEDR28") (class "Default")
      (node (ref "IC2") (pin "46") (pinfunction "OUTR9_46") (pintype "bidirectional"))
      (node (ref "LED28") (pin "4") (pinfunction "RED_4") (pintype "bidirectional"))
    )
    (net (code "297") (name "/N$LEDR29") (class "Default")
      (node (ref "IC2") (pin "5") (pinfunction "OUTR4_5") (pintype "bidirectional"))
      (node (ref "LED29") (pin "4") (pinfunction "RED_4") (pintype "bidirectional"))
    )
    (net (code "298") (name "/N$LEDR30") (class "Default")
      (node (ref "IC2") (pin "8") (pinfunction "OUTR0_8") (pintype "bidirectional"))
      (node (ref "LED30") (pin "4") (pinfunction "RED_4") (pintype "bidirectional"))
    )
    (net (code "299") (name "/N$LEDR31") (class "Default")
      (node (ref "IC2") (pin "49") (pinfunction "OUTR12_49") (pintype "bidirectional"))
      (node (ref "LED31") (pin "4") (pinfunction "RED_4") (pintype "bidirectional"))
    )
    (net (code "300") (name "/N$LEDR32") (class "Default")
      (node (ref "IC2") (pin "52") (pinfunction "OUTR8_52") (pintype "bidirectional"))
      (node (ref "LED32") (pin "4") (pinfunction "RED_4") (pintype "bidirectional"))
    )
    (net (code "301") (name "/N$LEDR33") (class "Default")
      (node (ref "IC3") (pin "26") (pinfunction "OUTR7_26") (pintype "bidirectional"))
      (node (ref "LED33") (pin "4") (pinfunction "RED_4") (pintype "bidirectional"))
    )
    (net (code "302") (name "/N$LEDR34") (class "Default")
      (node (ref "IC3") (pin "23") (pinfunction "OUTR3_23") (pintype "bidirectional"))
      (node (ref "LED34") (pin "4") (pinfunction "RED_4") (pintype "bidirectional"))
    )
    (net (code "303") (name "/N$LEDR35") (class "Default")
      (node (ref "IC3") (pin "31") (pinfunction "OUTR11_31") (pintype "bidirectional"))
      (node (ref "LED35") (pin "4") (pinfunction "RED_4") (pintype "bidirectional"))
    )
    (net (code "304") (name "/N$LEDR36") (class "Default")
      (node (ref "IC3") (pin "34") (pinfunction "OUTR15_34") (pintype "bidirectional"))
      (node (ref "LED36") (pin "4") (pinfunction "RED_4") (pintype "bidirectional"))
    )
    (net (code "305") (name "/N$LEDR37") (class "Default")
      (node (ref "IC3") (pin "20") (pinfunction "OUTR6_20") (pintype "bidirectional"))
      (node (ref "LED37") (pin "4") (pinfunction "RED_4") (pintype "bidirectional"))
    )
    (net (code "306") (name "/N$LEDR38") (class "Default")
      (node (ref "IC3") (pin "17") (pinfunction "OUTR2_17") (pintype "bidirectional"))
      (node (ref "LED38") (pin "4") (pinfunction "RED_4") (pintype "bidirectional"))
    )
    (net (code "307") (name "/N$LEDR39") (class "Default")
      (node (ref "IC3") (pin "37") (pinfunction "OUTR10_37") (pintype "bidirectional"))
      (node (ref "LED39") (pin "4") (pinfunction "RED_4") (pintype "bidirectional"))
    )
    (net (code "308") (name "/N$LEDR40") (class "Default")
      (node (ref "IC3") (pin "40") (pinfunction "OUTR14_40") (pintype "bidirectional"))
      (node (ref "LED40") (pin "4") (pinfunction "RED_4") (pintype "bidirectional"))
    )
    (net (code "309") (name "/N$LEDR41") (class "Default")
      (node (ref "IC3") (pin "14") (pinfunction "OUTR1_14") (pintype "bidirectional"))
      (node (ref "LED41") (pin "4") (pinfunction "RED_4") (pintype "bidirectional"))
    )
    (net (code "310") (name "/N$LEDR42") (class "Default")
      (node (ref "IC3") (pin "11") (pinfunction "OUTR5_11") (pintype "bidirectional"))
      (node (ref "LED42") (pin "4") (pinfunction "RED_4") (pintype "bidirectional"))
    )
    (net (code "311") (name "/N$LEDR43") (class "Default")
      (node (ref "IC3") (pin "43") (pinfunction "OUTR13_43") (pintype "bidirectional"))
      (node (ref "LED43") (pin "4") (pinfunction "RED_4") (pintype "bidirectional"))
    )
    (net (code "312") (name "/N$LEDR44") (class "Default")
      (node (ref "IC3") (pin "46") (pinfunction "OUTR9_46") (pintype "bidirectional"))
      (node (ref "LED44") (pin "4") (pinfunction "RED_4") (pintype "bidirectional"))
    )
    (net (code "313") (name "/N$LEDR45") (class "Default")
      (node (ref "IC3") (pin "5") (pinfunction "OUTR4_5") (pintype "bidirectional"))
      (node (ref "LED45") (pin "4") (pinfunction "RED_4") (pintype "bidirectional"))
    )
    (net (code "314") (name "/N$LEDR46") (class "Default")
      (node (ref "IC3") (pin "8") (pinfunction "OUTR0_8") (pintype "bidirectional"))
      (node (ref "LED46") (pin "4") (pinfunction "RED_4") (pintype "bidirectional"))
    )
    (net (code "315") (name "/N$LEDR47") (class "Default")
      (node (ref "IC3") (pin "49") (pinfunction "OUTR12_49") (pintype "bidirectional"))
      (node (ref "LED47") (pin "4") (pinfunction "RED_4") (pintype "bidirectional"))
    )
    (net (code "316") (name "/N$LEDR48") (class "Default")
      (node (ref "IC3") (pin "52") (pinfunction "OUTR8_52") (pintype "bidirectional"))
      (node (ref "LED48") (pin "4") (pinfunction "RED_4") (pintype "bidirectional"))
    )
    (net (code "317") (name "/N$LEDR49") (class "Default")
      (node (ref "IC4") (pin "26") (pinfunction "OUTR7_26") (pintype "bidirectional"))
      (node (ref "LED49") (pin "4") (pinfunction "RED_4") (pintype "bidirectional"))
    )
    (net (code "318") (name "/N$LEDR50") (class "Default")
      (node (ref "IC4") (pin "23") (pinfunction "OUTR3_23") (pintype "bidirectional"))
      (node (ref "LED50") (pin "4") (pinfunction "RED_4") (pintype "bidirectional"))
    )
    (net (code "319") (name "/N$LEDR51") (class "Default")
      (node (ref "IC4") (pin "31") (pinfunction "OUTR11_31") (pintype "bidirectional"))
      (node (ref "LED51") (pin "4") (pinfunction "RED_4") (pintype "bidirectional"))
    )
    (net (code "320") (name "/N$LEDR52") (class "Default")
      (node (ref "IC4") (pin "34") (pinfunction "OUTR15_34") (pintype "bidirectional"))
      (node (ref "LED52") (pin "4") (pinfunction "RED_4") (pintype "bidirectional"))
    )
    (net (code "321") (name "/N$LEDR53") (class "Default")
      (node (ref "IC4") (pin "20") (pinfunction "OUTR6_20") (pintype "bidirectional"))
      (node (ref "LED53") (pin "4") (pinfunction "RED_4") (pintype "bidirectional"))
    )
    (net (code "322") (name "/N$LEDR54") (class "Default")
      (node (ref "IC4") (pin "17") (pinfunction "OUTR2_17") (pintype "bidirectional"))
      (node (ref "LED54") (pin "4") (pinfunction "RED_4") (pintype "bidirectional"))
    )
    (net (code "323") (name "/N$LEDR55") (class "Default")
      (node (ref "IC4") (pin "37") (pinfunction "OUTR10_37") (pintype "bidirectional"))
      (node (ref "LED55") (pin "4") (pinfunction "RED_4") (pintype "bidirectional"))
    )
    (net (code "324") (name "/N$LEDR56") (class "Default")
      (node (ref "IC4") (pin "40") (pinfunction "OUTR14_40") (pintype "bidirectional"))
      (node (ref "LED56") (pin "4") (pinfunction "RED_4") (pintype "bidirectional"))
    )
    (net (code "325") (name "/N$LEDR57") (class "Default")
      (node (ref "IC4") (pin "14") (pinfunction "OUTR1_14") (pintype "bidirectional"))
      (node (ref "LED57") (pin "4") (pinfunction "RED_4") (pintype "bidirectional"))
    )
    (net (code "326") (name "/N$LEDR58") (class "Default")
      (node (ref "IC4") (pin "11") (pinfunction "OUTR5_11") (pintype "bidirectional"))
      (node (ref "LED58") (pin "4") (pinfunction "RED_4") (pintype "bidirectional"))
    )
    (net (code "327") (name "/N$LEDR59") (class "Default")
      (node (ref "IC4") (pin "43") (pinfunction "OUTR13_43") (pintype "bidirectional"))
      (node (ref "LED59") (pin "4") (pinfunction "RED_4") (pintype "bidirectional"))
    )
    (net (code "328") (name "/N$LEDR60") (class "Default")
      (node (ref "IC4") (pin "46") (pinfunction "OUTR9_46") (pintype "bidirectional"))
      (node (ref "LED60") (pin "4") (pinfunction "RED_4") (pintype "bidirectional"))
    )
    (net (code "329") (name "/N$LEDR61") (class "Default")
      (node (ref "IC4") (pin "5") (pinfunction "OUTR4_5") (pintype "bidirectional"))
      (node (ref "LED61") (pin "4") (pinfunction "RED_4") (pintype "bidirectional"))
    )
    (net (code "330") (name "/N$LEDR62") (class "Default")
      (node (ref "IC4") (pin "8") (pinfunction "OUTR0_8") (pintype "bidirectional"))
      (node (ref "LED62") (pin "4") (pinfunction "RED_4") (pintype "bidirectional"))
    )
    (net (code "331") (name "/N$LEDR63") (class "Default")
      (node (ref "IC4") (pin "49") (pinfunction "OUTR12_49") (pintype "bidirectional"))
      (node (ref "LED63") (pin "4") (pinfunction "RED_4") (pintype "bidirectional"))
    )
    (net (code "332") (name "/N$LEDR64") (class "Default")
      (node (ref "IC4") (pin "52") (pinfunction "OUTR8_52") (pintype "bidirectional"))
      (node (ref "LED64") (pin "4") (pinfunction "RED_4") (pintype "bidirectional"))
    )
    (net (code "333") (name "/N$LEDR65") (class "Default")
      (node (ref "IC5") (pin "26") (pinfunction "OUTR7_26") (pintype "bidirectional"))
      (node (ref "LED65") (pin "4") (pinfunction "RED_4") (pintype "bidirectional"))
    )
    (net (code "334") (name "/N$LEDR66") (class "Default")
      (node (ref "IC5") (pin "23") (pinfunction "OUTR3_23") (pintype "bidirectional"))
      (node (ref "LED66") (pin "4") (pinfunction "RED_4") (pintype "bidirectional"))
    )
    (net (code "335") (name "/N$LEDR67") (class "Default")
      (node (ref "IC5") (pin "31") (pinfunction "OUTR11_31") (pintype "bidirectional"))
      (node (ref "LED67") (pin "4") (pinfunction "RED_4") (pintype "bidirectional"))
    )
    (net (code "336") (name "/N$LEDR68") (class "Default")
      (node (ref "IC5") (pin "34") (pinfunction "OUTR15_34") (pintype "bidirectional"))
      (node (ref "LED68") (pin "4") (pinfunction "RED_4") (pintype "bidirectional"))
    )
    (net (code "337") (name "/N$LEDR69") (class "Default")
      (node (ref "IC5") (pin "20") (pinfunction "OUTR6_20") (pintype "bidirectional"))
      (node (ref "LED69") (pin "4") (pinfunction "RED_4") (pintype "bidirectional"))
    )
    (net (code "338") (name "/N$LEDR70") (class "Default")
      (node (ref "IC5") (pin "17") (pinfunction "OUTR2_17") (pintype "bidirectional"))
      (node (ref "LED70") (pin "4") (pinfunction "RED_4") (pintype "bidirectional"))
    )
    (net (code "339") (name "/N$LEDR71") (class "Default")
      (node (ref "IC5") (pin "37") (pinfunction "OUTR10_37") (pintype "bidirectional"))
      (node (ref "LED71") (pin "4") (pinfunction "RED_4") (pintype "bidirectional"))
    )
    (net (code "340") (name "/N$LEDR72") (class "Default")
      (node (ref "IC5") (pin "40") (pinfunction "OUTR14_40") (pintype "bidirectional"))
      (node (ref "LED72") (pin "4") (pinfunction "RED_4") (pintype "bidirectional"))
    )
    (net (code "341") (name "/N$LEDR73") (class "Default")
      (node (ref "IC5") (pin "14") (pinfunction "OUTR1_14") (pintype "bidirectional"))
      (node (ref "LED73") (pin "4") (pinfunction "RED_4") (pintype "bidirectional"))
    )
    (net (code "342") (name "/N$LEDR74") (class "Default")
      (node (ref "IC5") (pin "11") (pinfunction "OUTR5_11") (pintype "bidirectional"))
      (node (ref "LED74") (pin "4") (pinfunction "RED_4") (pintype "bidirectional"))
    )
    (net (code "343") (name "/N$LEDR75") (class "Default")
      (node (ref "IC5") (pin "43") (pinfunction "OUTR13_43") (pintype "bidirectional"))
      (node (ref "LED75") (pin "4") (pinfunction "RED_4") (pintype "bidirectional"))
    )
    (net (code "344") (name "/N$LEDR76") (class "Default")
      (node (ref "IC5") (pin "46") (pinfunction "OUTR9_46") (pintype "bidirectional"))
      (node (ref "LED76") (pin "4") (pinfunction "RED_4") (pintype "bidirectional"))
    )
    (net (code "345") (name "/N$LEDR77") (class "Default")
      (node (ref "IC5") (pin "5") (pinfunction "OUTR4_5") (pintype "bidirectional"))
      (node (ref "LED77") (pin "4") (pinfunction "RED_4") (pintype "bidirectional"))
    )
    (net (code "346") (name "/N$LEDR78") (class "Default")
      (node (ref "IC5") (pin "8") (pinfunction "OUTR0_8") (pintype "bidirectional"))
      (node (ref "LED78") (pin "4") (pinfunction "RED_4") (pintype "bidirectional"))
    )
    (net (code "347") (name "/N$LEDR79") (class "Default")
      (node (ref "IC5") (pin "49") (pinfunction "OUTR12_49") (pintype "bidirectional"))
      (node (ref "LED79") (pin "4") (pinfunction "RED_4") (pintype "bidirectional"))
    )
    (net (code "348") (name "/N$LEDR80") (class "Default")
      (node (ref "IC5") (pin "52") (pinfunction "OUTR8_52") (pintype "bidirectional"))
      (node (ref "LED80") (pin "4") (pinfunction "RED_4") (pintype "bidirectional"))
    )
    (net (code "349") (name "/N$LEDR81") (class "Default")
      (node (ref "IC6") (pin "26") (pinfunction "OUTR7_26") (pintype "bidirectional"))
      (node (ref "LED81") (pin "4") (pinfunction "RED_4") (pintype "bidirectional"))
    )
    (net (code "350") (name "/N$LEDR82") (class "Default")
      (node (ref "IC6") (pin "23") (pinfunction "OUTR3_23") (pintype "bidirectional"))
      (node (ref "LED82") (pin "4") (pinfunction "RED_4") (pintype "bidirectional"))
    )
    (net (code "351") (name "/N$LEDR83") (class "Default")
      (node (ref "IC6") (pin "31") (pinfunction "OUTR11_31") (pintype "bidirectional"))
      (node (ref "LED83") (pin "4") (pinfunction "RED_4") (pintype "bidirectional"))
    )
    (net (code "352") (name "/N$LEDR84") (class "Default")
      (node (ref "IC6") (pin "34") (pinfunction "OUTR15_34") (pintype "bidirectional"))
      (node (ref "LED84") (pin "4") (pinfunction "RED_4") (pintype "bidirectional"))
    )
    (net (code "353") (name "/N$LEDR85") (class "Default")
      (node (ref "IC6") (pin "20") (pinfunction "OUTR6_20") (pintype "bidirectional"))
      (node (ref "LED85") (pin "4") (pinfunction "RED_4") (pintype "bidirectional"))
    )
    (net (code "354") (name "/N$LEDR86") (class "Default")
      (node (ref "IC6") (pin "17") (pinfunction "OUTR2_17") (pintype "bidirectional"))
      (node (ref "LED86") (pin "4") (pinfunction "RED_4") (pintype "bidirectional"))
    )
    (net (code "355") (name "/N$LEDR87") (class "Default")
      (node (ref "IC6") (pin "37") (pinfunction "OUTR10_37") (pintype "bidirectional"))
      (node (ref "LED87") (pin "4") (pinfunction "RED_4") (pintype "bidirectional"))
    )
    (net (code "356") (name "/N$LEDR88") (class "Default")
      (node (ref "IC6") (pin "40") (pinfunction "OUTR14_40") (pintype "bidirectional"))
      (node (ref "LED88") (pin "4") (pinfunction "RED_4") (pintype "bidirectional"))
    )
    (net (code "357") (name "/N$LEDR89") (class "Default")
      (node (ref "IC6") (pin "14") (pinfunction "OUTR1_14") (pintype "bidirectional"))
      (node (ref "LED89") (pin "4") (pinfunction "RED_4") (pintype "bidirectional"))
    )
    (net (code "358") (name "/N$LEDR90") (class "Default")
      (node (ref "IC6") (pin "11") (pinfunction "OUTR5_11") (pintype "bidirectional"))
      (node (ref "LED90") (pin "4") (pinfunction "RED_4") (pintype "bidirectional"))
    )
    (net (code "359") (name "/N$LEDR91") (class "Default")
      (node (ref "IC6") (pin "43") (pinfunction "OUTR13_43") (pintype "bidirectional"))
      (node (ref "LED91") (pin "4") (pinfunction "RED_4") (pintype "bidirectional"))
    )
    (net (code "360") (name "/N$LEDR92") (class "Default")
      (node (ref "IC6") (pin "46") (pinfunction "OUTR9_46") (pintype "bidirectional"))
      (node (ref "LED92") (pin "4") (pinfunction "RED_4") (pintype "bidirectional"))
    )
    (net (code "361") (name "/N$LEDR93") (class "Default")
      (node (ref "IC6") (pin "5") (pinfunction "OUTR4_5") (pintype "bidirectional"))
      (node (ref "LED93") (pin "4") (pinfunction "RED_4") (pintype "bidirectional"))
    )
    (net (code "362") (name "/N$LEDR94") (class "Default")
      (node (ref "IC6") (pin "8") (pinfunction "OUTR0_8") (pintype "bidirectional"))
      (node (ref "LED94") (pin "4") (pinfunction "RED_4") (pintype "bidirectional"))
    )
    (net (code "363") (name "/N$LEDR95") (class "Default")
      (node (ref "IC6") (pin "49") (pinfunction "OUTR12_49") (pintype "bidirectional"))
      (node (ref "LED95") (pin "4") (pinfunction "RED_4") (pintype "bidirectional"))
    )
    (net (code "364") (name "/N$LEDR96") (class "Default")
      (node (ref "IC6") (pin "52") (pinfunction "OUTR8_52") (pintype "bidirectional"))
      (node (ref "LED96") (pin "4") (pinfunction "RED_4") (pintype "bidirectional"))
    )
    (net (code "365") (name "/N$LEDR97") (class "Default")
      (node (ref "IC7") (pin "26") (pinfunction "OUTR7_26") (pintype "bidirectional"))
      (node (ref "LED97") (pin "4") (pinfunction "RED_4") (pintype "bidirectional"))
    )
    (net (code "366") (name "/N$LEDR98") (class "Default")
      (node (ref "IC7") (pin "23") (pinfunction "OUTR3_23") (pintype "bidirectional"))
      (node (ref "LED98") (pin "4") (pinfunction "RED_4") (pintype "bidirectional"))
    )
    (net (code "367") (name "/N$LEDR99") (class "Default")
      (node (ref "IC7") (pin "31") (pinfunction "OUTR11_31") (pintype "bidirectional"))
      (node (ref "LED99") (pin "4") (pinfunction "RED_4") (pintype "bidirectional"))
    )
    (net (code "368") (name "/N$LEDR100") (class "Default")
      (node (ref "IC7") (pin "34") (pinfunction "OUTR15_34") (pintype "bidirectional"))
      (node (ref "LED100") (pin "4") (pinfunction "RED_4") (pintype "bidirectional"))
    )
    (net (code "369") (name "/N$LEDR101") (class "Default")
      (node (ref "IC7") (pin "20") (pinfunction "OUTR6_20") (pintype "bidirectional"))
      (node (ref "LED101") (pin "4") (pinfunction "RED_4") (pintype "bidirectional"))
    )
    (net (code "370") (name "/N$LEDR102") (class "Default")
      (node (ref "IC7") (pin "17") (pinfunction "OUTR2_17") (pintype "bidirectional"))
      (node (ref "LED102") (pin "4") (pinfunction "RED_4") (pintype "bidirectional"))
    )
    (net (code "371") (name "/N$LEDR103") (class "Default")
      (node (ref "IC7") (pin "37") (pinfunction "OUTR10_37") (pintype "bidirectional"))
      (node (ref "LED103") (pin "4") (pinfunction "RED_4") (pintype "bidirectional"))
    )
    (net (code "372") (name "/N$LEDR104") (class "Default")
      (node (ref "IC7") (pin "40") (pinfunction "OUTR14_40") (pintype "bidirectional"))
      (node (ref "LED104") (pin "4") (pinfunction "RED_4") (pintype "bidirectional"))
    )
    (net (code "373") (name "/N$LEDR105") (class "Default")
      (node (ref "IC7") (pin "14") (pinfunction "OUTR1_14") (pintype "bidirectional"))
      (node (ref "LED105") (pin "4") (pinfunction "RED_4") (pintype "bidirectional"))
    )
    (net (code "374") (name "/N$LEDR106") (class "Default")
      (node (ref "IC7") (pin "11") (pinfunction "OUTR5_11") (pintype "bidirectional"))
      (node (ref "LED106") (pin "4") (pinfunction "RED_4") (pintype "bidirectional"))
    )
    (net (code "375") (name "/N$LEDR107") (class "Default")
      (node (ref "IC7") (pin "43") (pinfunction "OUTR13_43") (pintype "bidirectional"))
      (node (ref "LED107") (pin "4") (pinfunction "RED_4") (pintype "bidirectional"))
    )
    (net (code "376") (name "/N$LEDR108") (class "Default")
      (node (ref "IC7") (pin "46") (pinfunction "OUTR9_46") (pintype "bidirectional"))
      (node (ref "LED108") (pin "4") (pinfunction "RED_4") (pintype "bidirectional"))
    )
    (net (code "377") (name "/N$LEDR109") (class "Default")
      (node (ref "IC7") (pin "5") (pinfunction "OUTR4_5") (pintype "bidirectional"))
      (node (ref "LED109") (pin "4") (pinfunction "RED_4") (pintype "bidirectional"))
    )
    (net (code "378") (name "/N$LEDR110") (class "Default")
      (node (ref "IC7") (pin "8") (pinfunction "OUTR0_8") (pintype "bidirectional"))
      (node (ref "LED110") (pin "4") (pinfunction "RED_4") (pintype "bidirectional"))
    )
    (net (code "379") (name "/N$LEDR111") (class "Default")
      (node (ref "IC7") (pin "49") (pinfunction "OUTR12_49") (pintype "bidirectional"))
      (node (ref "LED111") (pin "4") (pinfunction "RED_4") (pintype "bidirectional"))
    )
    (net (code "380") (name "/N$LEDR112") (class "Default")
      (node (ref "IC7") (pin "52") (pinfunction "OUTR8_52") (pintype "bidirectional"))
      (node (ref "LED112") (pin "4") (pinfunction "RED_4") (pintype "bidirectional"))
    )
    (net (code "381") (name "/N$LEDR113") (class "Default")
      (node (ref "IC8") (pin "26") (pinfunction "OUTR7_26") (pintype "bidirectional"))
      (node (ref "LED113") (pin "4") (pinfunction "RED_4") (pintype "bidirectional"))
    )
    (net (code "382") (name "/N$LEDR114") (class "Default")
      (node (ref "IC8") (pin "23") (pinfunction "OUTR3_23") (pintype "bidirectional"))
      (node (ref "LED114") (pin "4") (pinfunction "RED_4") (pintype "bidirectional"))
    )
    (net (code "383") (name "/N$LEDR115") (class "Default")
      (node (ref "IC8") (pin "31") (pinfunction "OUTR11_31") (pintype "bidirectional"))
      (node (ref "LED115") (pin "4") (pinfunction "RED_4") (pintype "bidirectional"))
    )
    (net (code "384") (name "/N$LEDR116") (class "Default")
      (node (ref "IC8") (pin "34") (pinfunction "OUTR15_34") (pintype "bidirectional"))
      (node (ref "LED116") (pin "4") (pinfunction "RED_4") (pintype "bidirectional"))
    )
    (net (code "385") (name "/N$LEDR117") (class "Default")
      (node (ref "IC8") (pin "20") (pinfunction "OUTR6_20") (pintype "bidirectional"))
      (node (ref "LED117") (pin "4") (pinfunction "RED_4") (pintype "bidirectional"))
    )
    (net (code "386") (name "/N$LEDR118") (class "Default")
      (node (ref "IC8") (pin "17") (pinfunction "OUTR2_17") (pintype "bidirectional"))
      (node (ref "LED118") (pin "4") (pinfunction "RED_4") (pintype "bidirectional"))
    )
    (net (code "387") (name "/N$LEDR119") (class "Default")
      (node (ref "IC8") (pin "37") (pinfunction "OUTR10_37") (pintype "bidirectional"))
      (node (ref "LED119") (pin "4") (pinfunction "RED_4") (pintype "bidirectional"))
    )
    (net (code "388") (name "/N$LEDR120") (class "Default")
      (node (ref "IC8") (pin "40") (pinfunction "OUTR14_40") (pintype "bidirectional"))
      (node (ref "LED120") (pin "4") (pinfunction "RED_4") (pintype "bidirectional"))
    )
    (net (code "389") (name "/SCLK") (class "Default")
      (node (ref "IC1") (pin "2") (pinfunction "SCLK_2") (pintype "bidirectional"))
      (node (ref "IC2") (pin "2") (pinfunction "SCLK_2") (pintype "bidirectional"))
      (node (ref "IC3") (pin "2") (pinfunction "SCLK_2") (pintype "bidirectional"))
      (node (ref "IC4") (pin "2") (pinfunction "SCLK_2") (pintype "bidirectional"))
      (node (ref "IC5") (pin "2") (pinfunction "SCLK_2") (pintype "bidirectional"))
      (node (ref "IC6") (pin "2") (pinfunction "SCLK_2") (pintype "bidirectional"))
      (node (ref "IC7") (pin "2") (pinfunction "SCLK_2") (pintype "bidirectional"))
      (node (ref "IC8") (pin "2") (pinfunction "SCLK_2") (pintype "bidirectional"))
      (node (ref "SV1") (pin "1") (pinfunction "1_1") (pintype "passive"))
    )
    (net (code "390") (name "/SIN_1,2") (class "Default")
      (node (ref "IC2") (pin "1") (pinfunction "SIN_1") (pintype "bidirectional"))
      (node (ref "SV1") (pin "2") (pinfunction "2_2") (pintype "passive"))
    )
    (net (code "391") (name "/SIN_3,4") (class "Default")
      (node (ref "IC4") (pin "1") (pinfunction "SIN_1") (pintype "bidirectional"))
      (node (ref "SV1") (pin "3") (pinfunction "3_3") (pintype "passive"))
    )
    (net (code "392") (name "/SIN_5,6") (class "Default")
      (node (ref "IC6") (pin "1") (pinfunction "SIN_1") (pintype "bidirectional"))
      (node (ref "SV1") (pin "4") (pinfunction "4_4") (pintype "passive"))
    )
    (net (code "393") (name "/SIN_7,8") (class "Default")
      (node (ref "IC8") (pin "1") (pinfunction "SIN_1") (pintype "bidirectional"))
      (node (ref "SV1") (pin "7") (pinfunction "7_7") (pintype "passive"))
    )
    (net (code "394") (name "/SOUT1") (class "Default")
      (node (ref "IC1") (pin "28") (pinfunction "SOUT_28") (pintype "bidirectional"))
    )
    (net (code "395") (name "/SOUT2") (class "Default")
      (node (ref "IC1") (pin "1") (pinfunction "SIN_1") (pintype "bidirectional"))
      (node (ref "IC2") (pin "28") (pinfunction "SOUT_28") (pintype "bidirectional"))
    )
    (net (code "396") (name "/SOUT3") (class "Default")
      (node (ref "IC3") (pin "28") (pinfunction "SOUT_28") (pintype "bidirectional"))
    )
    (net (code "397") (name "/SOUT4") (class "Default")
      (node (ref "IC3") (pin "1") (pinfunction "SIN_1") (pintype "bidirectional"))
      (node (ref "IC4") (pin "28") (pinfunction "SOUT_28") (pintype "bidirectional"))
    )
    (net (code "398") (name "/SOUT5") (class "Default")
      (node (ref "IC5") (pin "28") (pinfunction "SOUT_28") (pintype "bidirectional"))
    )
    (net (code "399") (name "/SOUT6") (class "Default")
      (node (ref "IC5") (pin "1") (pinfunction "SIN_1") (pintype "bidirectional"))
      (node (ref "IC6") (pin "28") (pinfunction "SOUT_28") (pintype "bidirectional"))
    )
    (net (code "400") (name "/SOUT7") (class "Default")
      (node (ref "IC7") (pin "28") (pinfunction "SOUT_28") (pintype "bidirectional"))
    )
    (net (code "401") (name "/SOUT8") (class "Default")
      (node (ref "IC7") (pin "1") (pinfunction "SIN_1") (pintype "bidirectional"))
      (node (ref "IC8") (pin "28") (pinfunction "SOUT_28") (pintype "bidirectional"))
    )
  )
)
